# schmequencer.net
KiCad netlist of a schematic drawn in EAGLE
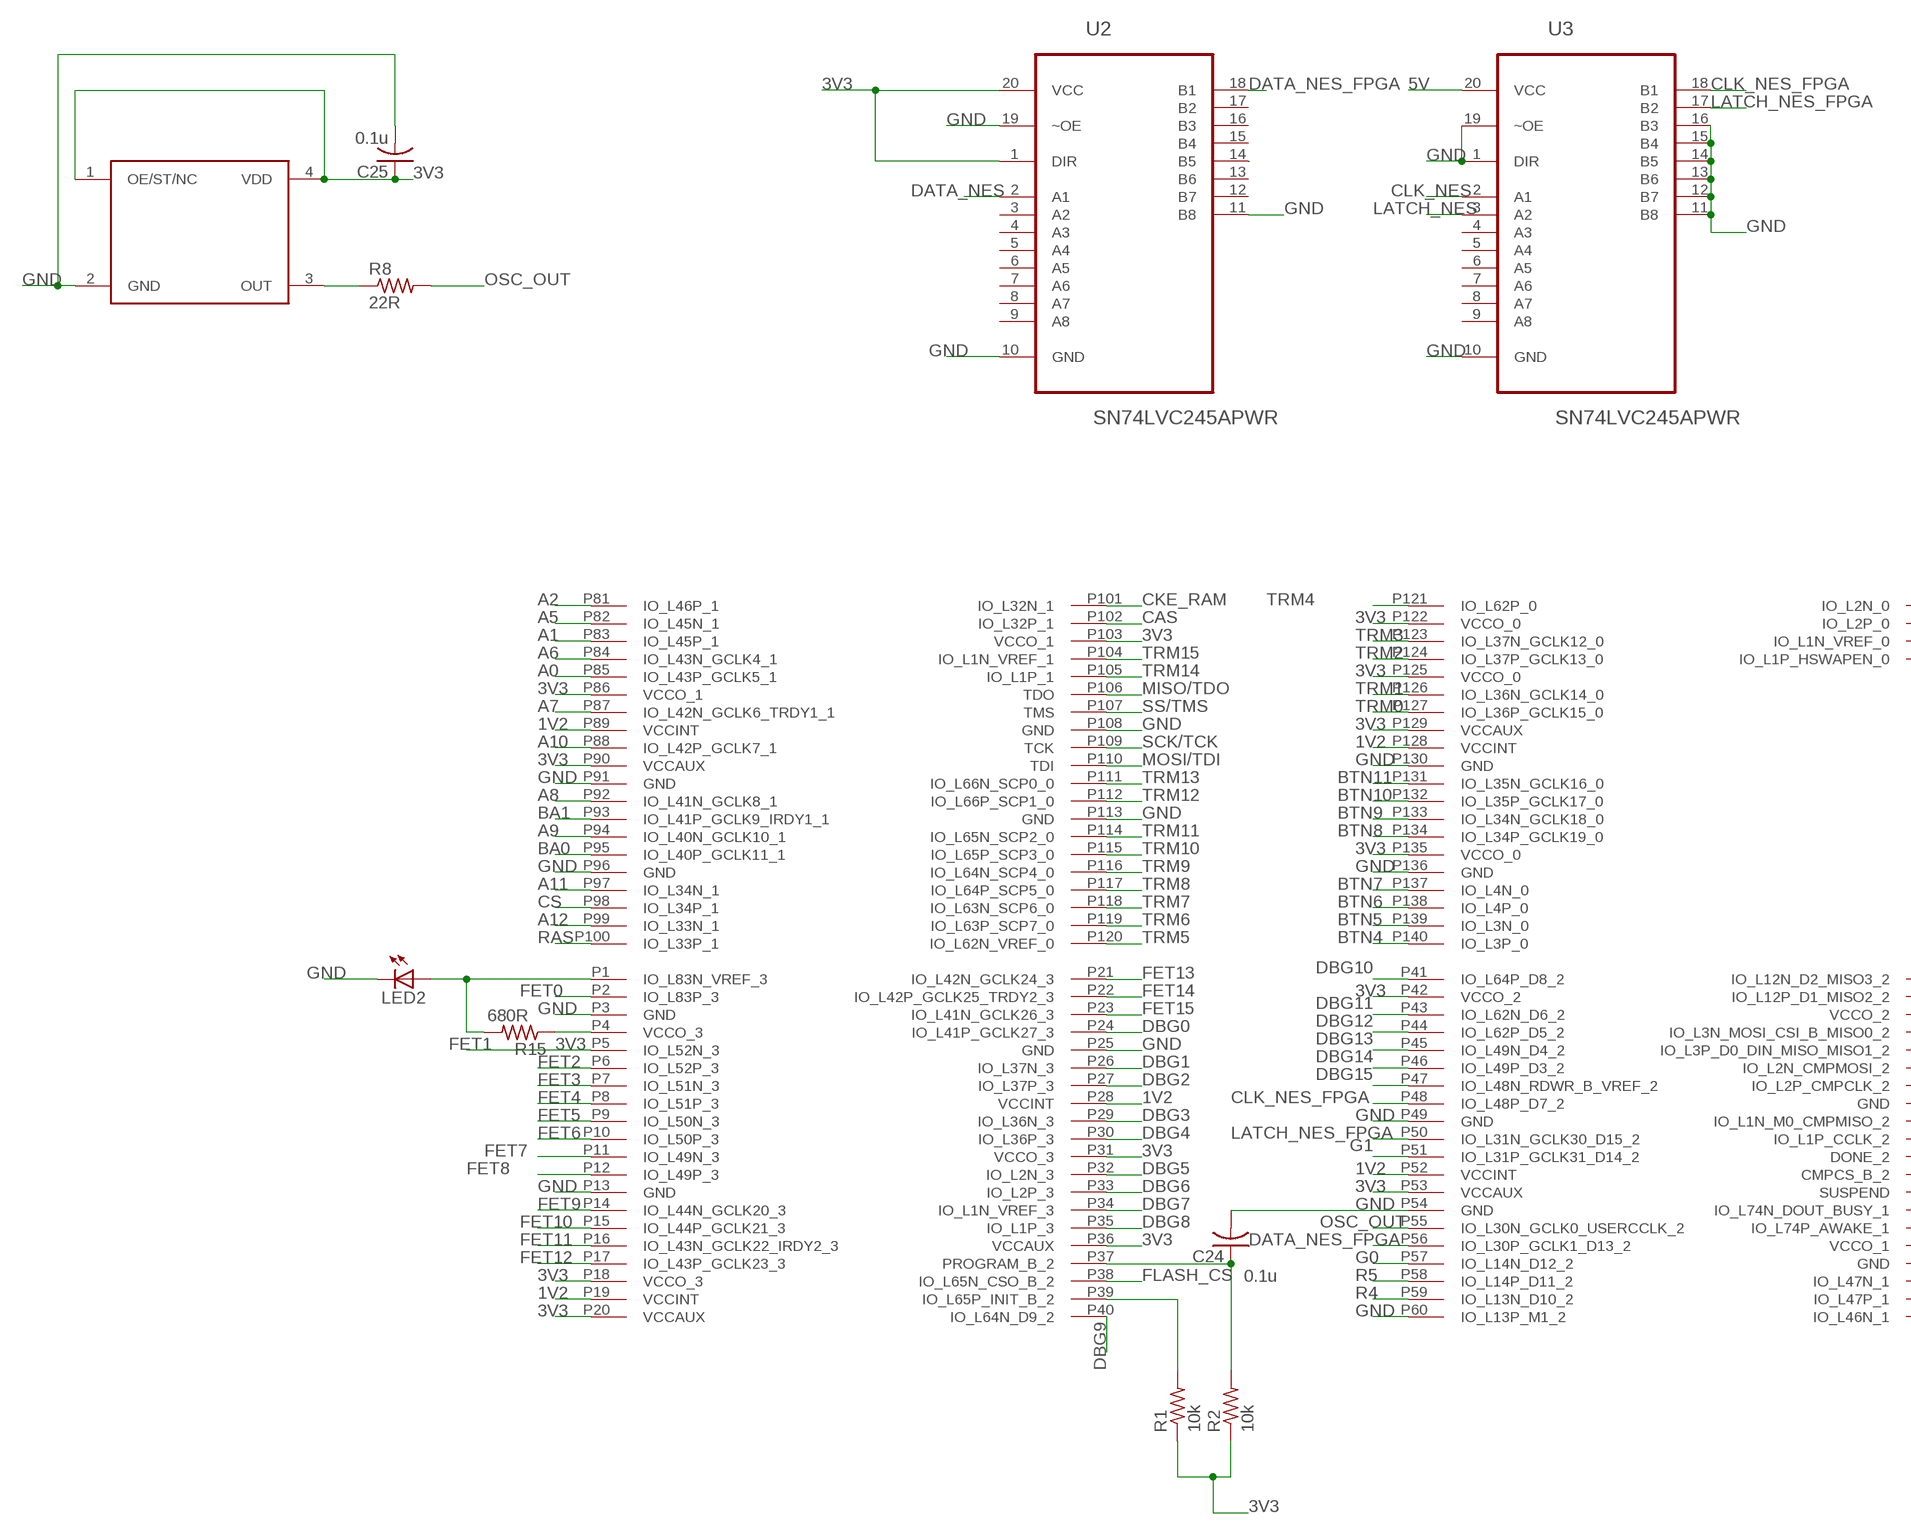
[diagram p0: schematic, sheet 1, part 1 of 2]
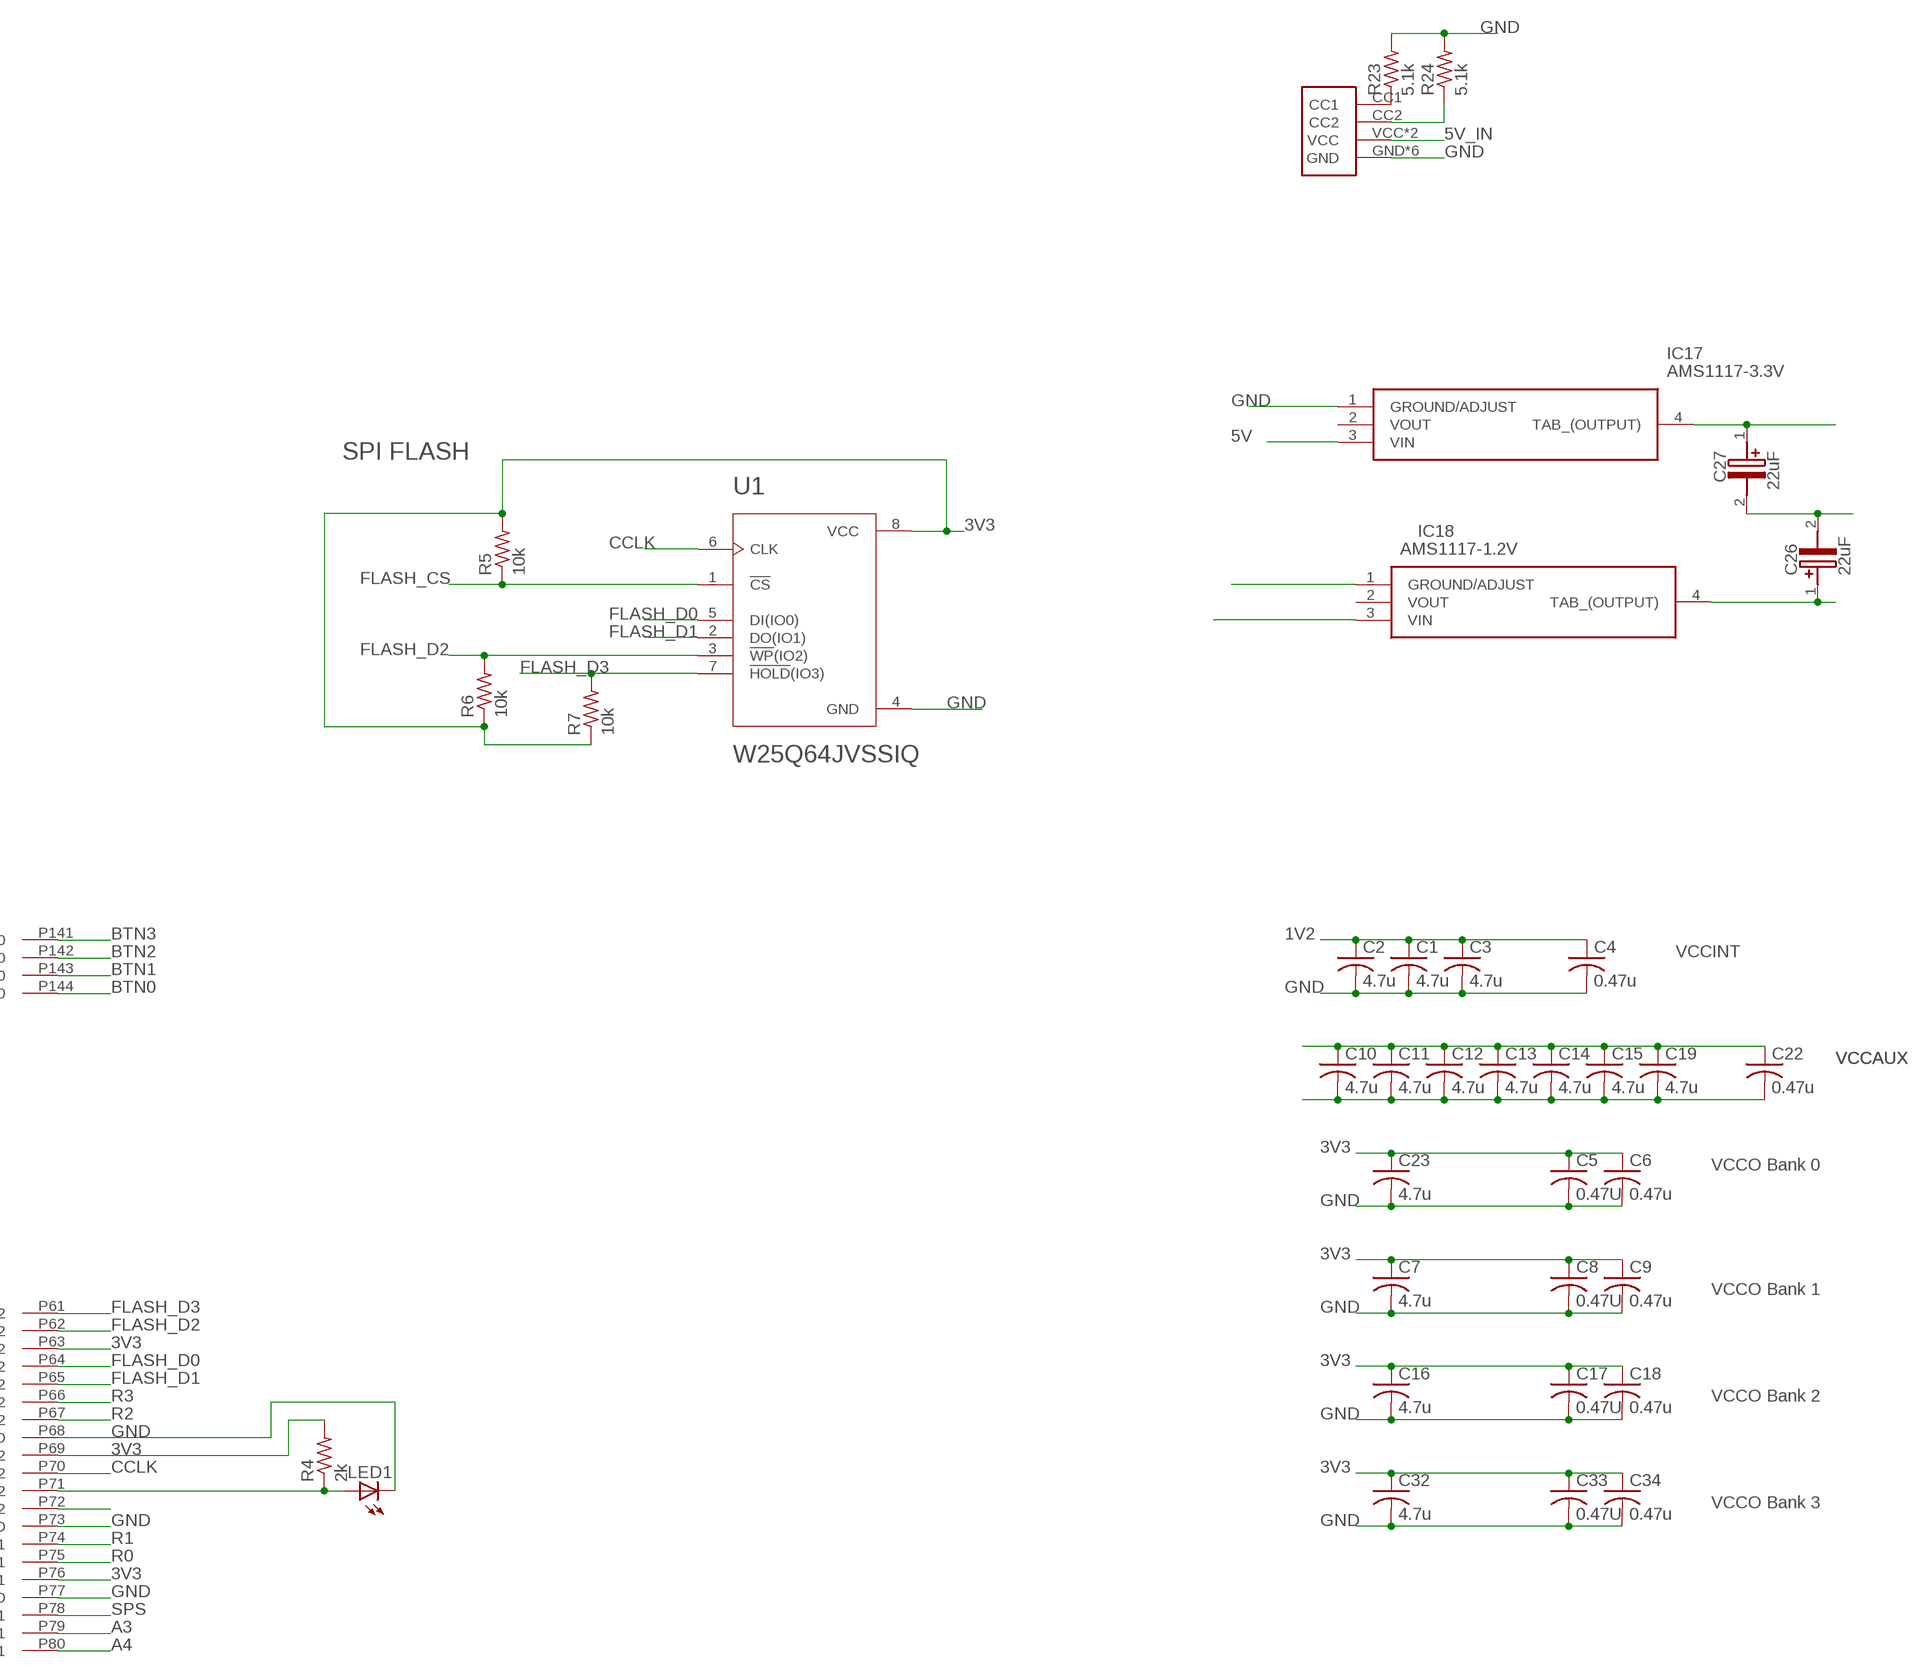
[diagram p1: schematic, sheet 1, part 2 of 2]
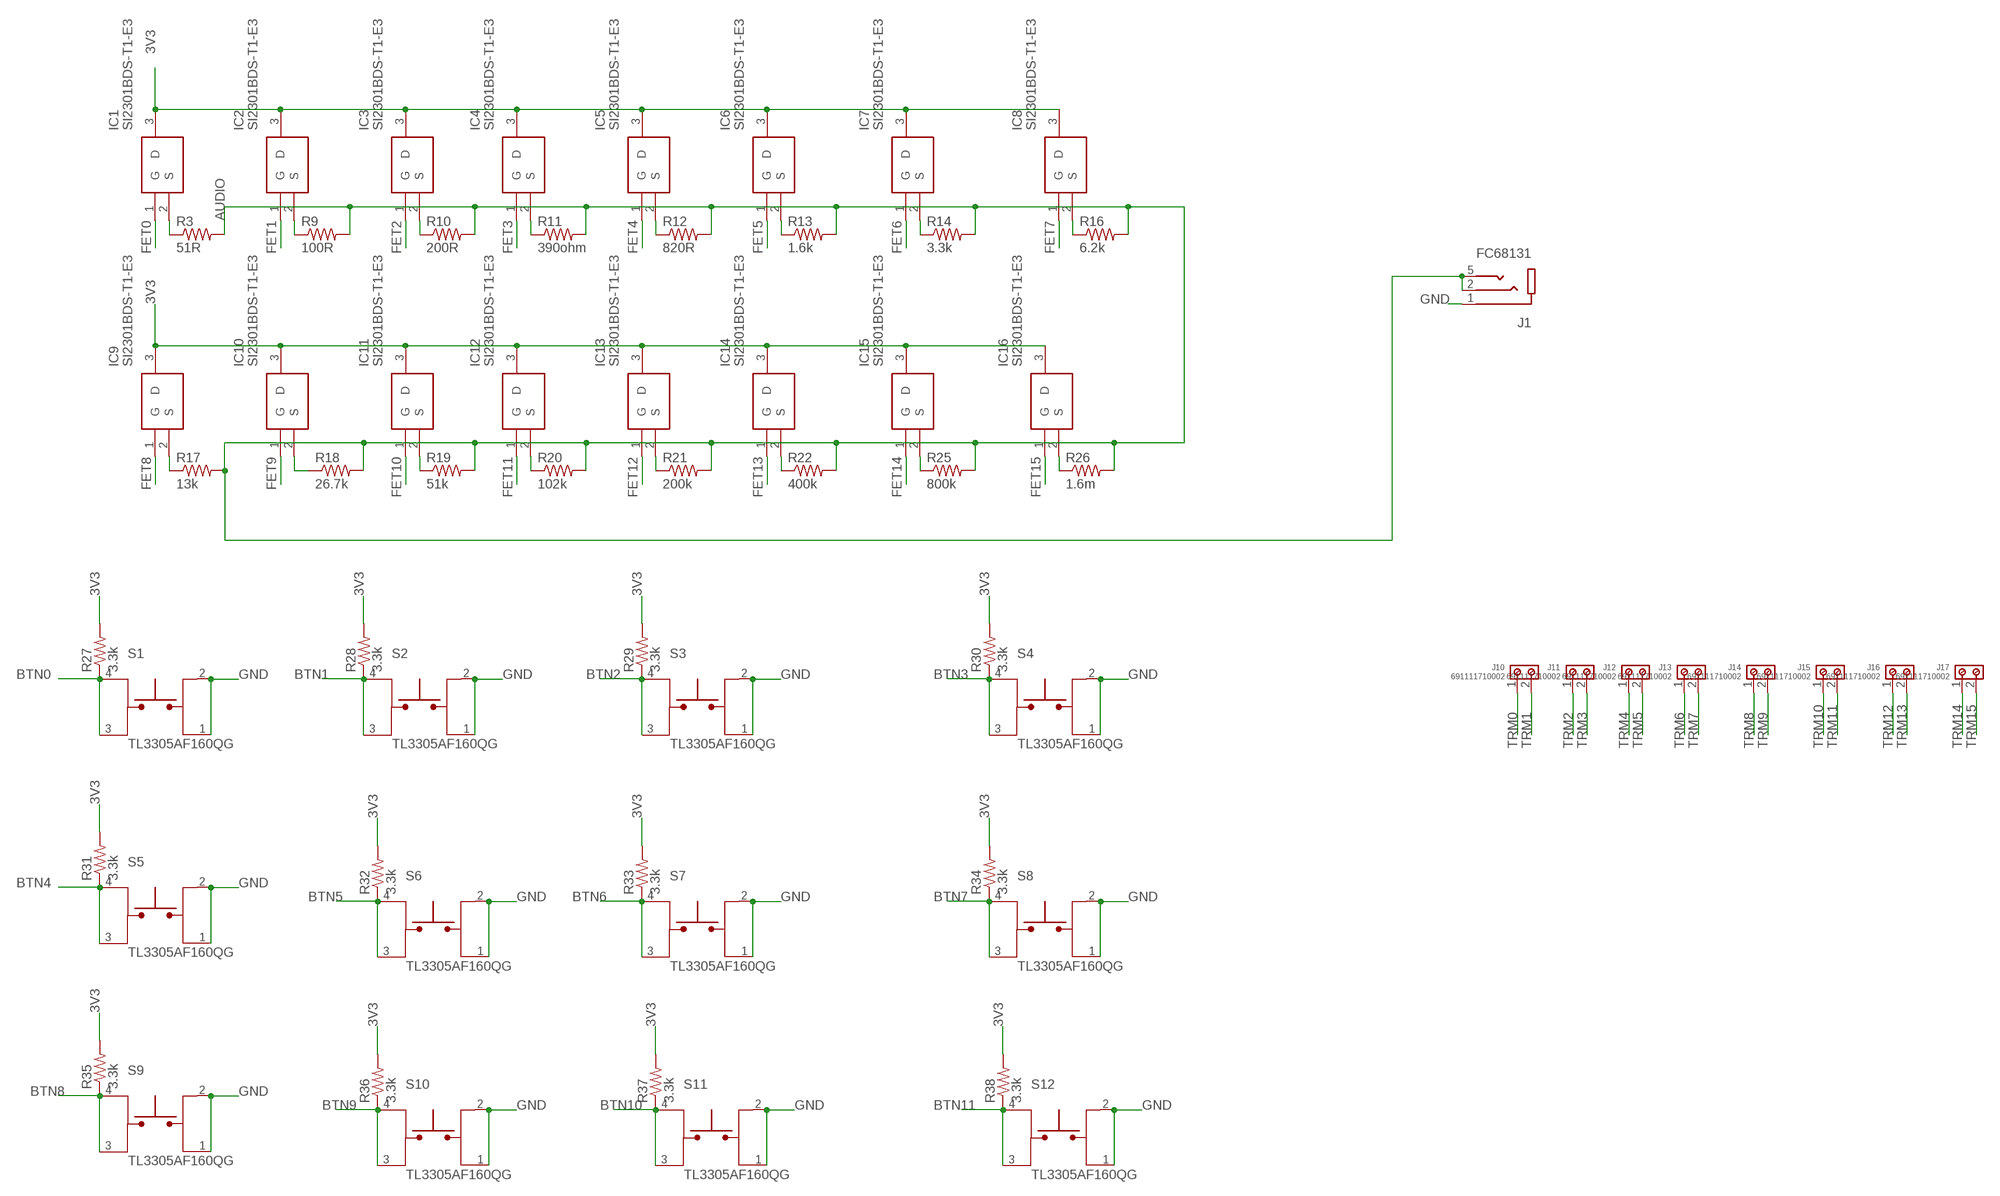
[diagram p2: schematic, sheet 2]
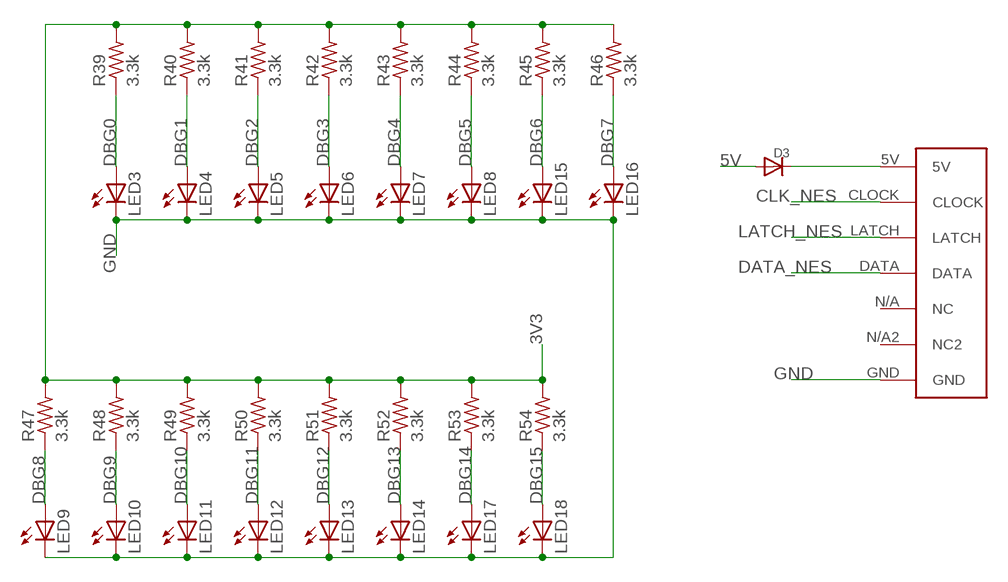
[diagram p3: schematic, sheet 3]

(export (version "E")
  (design (tool "Eeschema 10.0.6"))
  (components
    (comp (ref "C1")
      (value "4.7u")
      (footprint "eagle-import:C0603")
      (libsource (lib "eagle-import") (part "C-USC0603"))
    )
    (comp (ref "C2")
      (value "4.7u")
      (footprint "eagle-import:C0603")
      (libsource (lib "eagle-import") (part "C-USC0603"))
    )
    (comp (ref "C3")
      (value "4.7u")
      (footprint "eagle-import:C0603")
      (libsource (lib "eagle-import") (part "C-USC0603"))
    )
    (comp (ref "C4")
      (value "0.47u")
      (footprint "eagle-import:C0603")
      (libsource (lib "eagle-import") (part "C-USC0603"))
    )
    (comp (ref "C5")
      (value "0.47U")
      (footprint "eagle-import:C0603")
      (libsource (lib "eagle-import") (part "C-USC0603"))
    )
    (comp (ref "C6")
      (value "0.47u")
      (footprint "eagle-import:C0603")
      (libsource (lib "eagle-import") (part "C-USC0603"))
    )
    (comp (ref "C7")
      (value "4.7u")
      (footprint "eagle-import:C0603")
      (libsource (lib "eagle-import") (part "C-USC0603"))
    )
    (comp (ref "C8")
      (value "0.47U")
      (footprint "eagle-import:C0603")
      (libsource (lib "eagle-import") (part "C-USC0603"))
    )
    (comp (ref "C9")
      (value "0.47u")
      (footprint "eagle-import:C0603")
      (libsource (lib "eagle-import") (part "C-USC0603"))
    )
    (comp (ref "C10")
      (value "4.7u")
      (footprint "eagle-import:C0603")
      (libsource (lib "eagle-import") (part "C-USC0603"))
    )
    (comp (ref "C11")
      (value "4.7u")
      (footprint "eagle-import:C0603")
      (libsource (lib "eagle-import") (part "C-USC0603"))
    )
    (comp (ref "C12")
      (value "4.7u")
      (footprint "eagle-import:C0603")
      (libsource (lib "eagle-import") (part "C-USC0603"))
    )
    (comp (ref "C13")
      (value "4.7u")
      (footprint "eagle-import:C0603")
      (libsource (lib "eagle-import") (part "C-USC0603"))
    )
    (comp (ref "C14")
      (value "4.7u")
      (footprint "eagle-import:C0603")
      (libsource (lib "eagle-import") (part "C-USC0603"))
    )
    (comp (ref "C15")
      (value "4.7u")
      (footprint "eagle-import:C0603")
      (libsource (lib "eagle-import") (part "C-USC0603"))
    )
    (comp (ref "C16")
      (value "4.7u")
      (footprint "eagle-import:C0603")
      (libsource (lib "eagle-import") (part "C-USC0603"))
    )
    (comp (ref "C17")
      (value "0.47U")
      (footprint "eagle-import:C0603")
      (libsource (lib "eagle-import") (part "C-USC0603"))
    )
    (comp (ref "C18")
      (value "0.47u")
      (footprint "eagle-import:C0603")
      (libsource (lib "eagle-import") (part "C-USC0603"))
    )
    (comp (ref "C19")
      (value "4.7u")
      (footprint "eagle-import:C0603")
      (libsource (lib "eagle-import") (part "C-USC0603"))
    )
    (comp (ref "C22")
      (value "0.47u")
      (footprint "eagle-import:C0603")
      (libsource (lib "eagle-import") (part "C-USC0603"))
    )
    (comp (ref "C23")
      (value "4.7u")
      (footprint "eagle-import:C0603")
      (libsource (lib "eagle-import") (part "C-USC0603"))
    )
    (comp (ref "C24")
      (value "0.1u")
      (footprint "eagle-import:C0603")
      (libsource (lib "eagle-import") (part "C-USC0603"))
    )
    (comp (ref "C25")
      (value "0.1u")
      (footprint "eagle-import:C0603")
      (libsource (lib "eagle-import") (part "C-USC0603"))
    )
    (comp (ref "C26")
      (value "22uF")
      (footprint "eagle-import:CAPPM3216X180N")
      (fields
        (field (name "MANUFACTURER_PART_NUMBER") "293D106X9016A2TE3")
        (field (name "MOUSER2_PART_NUMBER") "74-293D106X9016A2TE3")
      )
      (libsource (lib "eagle-import") (part "293D106X9016A2TE3"))
    )
    (comp (ref "C27")
      (value "22uF")
      (footprint "eagle-import:CAPPM3216X180N")
      (fields
        (field (name "MANUFACTURER_PART_NUMBER") "293D106X9016A2TE3")
        (field (name "MOUSER2_PART_NUMBER") "74-293D106X9016A2TE3")
      )
      (libsource (lib "eagle-import") (part "293D106X9016A2TE3"))
    )
    (comp (ref "C32")
      (value "4.7u")
      (footprint "eagle-import:C0603")
      (libsource (lib "eagle-import") (part "C-USC0603"))
    )
    (comp (ref "C33")
      (value "0.47U")
      (footprint "eagle-import:C0603")
      (libsource (lib "eagle-import") (part "C-USC0603"))
    )
    (comp (ref "C34")
      (value "0.47u")
      (footprint "eagle-import:C0603")
      (libsource (lib "eagle-import") (part "C-USC0603"))
    )
    (comp (ref "IC17")
      (value "AMS1117-3.3V")
      (footprint "eagle-import:SOT229P700X180-4N")
      (fields (field (name "MANUFACTURER_PART_NUMBER") "ams1117-3.3v"))
      (libsource (lib "eagle-import") (part "AMS1117-3.3V"))
    )
    (comp (ref "IC18")
      (value "AMS1117-1.2V")
      (footprint "eagle-import:SOT229P700X180-4N")
      (fields (field (name "MANUFACTURER_PART_NUMBER") "ams1117-3.3v"))
      (libsource (lib "eagle-import") (part "AMS1117-3.3V"))
    )
    (comp (ref "LED1")
      (value "LEDCHIP-LED0603")
      (footprint "eagle-import:CHIP-LED0603")
      (libsource (lib "eagle-import") (part "LEDCHIP-LED0603"))
    )
    (comp (ref "LED2")
      (value "LEDCHIP-LED0603")
      (footprint "eagle-import:CHIP-LED0603")
      (libsource (lib "eagle-import") (part "LEDCHIP-LED0603"))
    )
    (comp (ref "R1")
      (value "10k")
      (footprint "eagle-import:R0603")
      (libsource (lib "eagle-import") (part "R-US_R0603"))
    )
    (comp (ref "R2")
      (value "10k")
      (footprint "eagle-import:R0603")
      (libsource (lib "eagle-import") (part "R-US_R0603"))
    )
    (comp (ref "R4")
      (value "2k")
      (footprint "eagle-import:R0603")
      (libsource (lib "eagle-import") (part "R-US_R0603"))
    )
    (comp (ref "R5")
      (value "10k")
      (footprint "eagle-import:R0603")
      (libsource (lib "eagle-import") (part "R-US_R0603"))
    )
    (comp (ref "R6")
      (value "10k")
      (footprint "eagle-import:R0603")
      (libsource (lib "eagle-import") (part "R-US_R0603"))
    )
    (comp (ref "R7")
      (value "10k")
      (footprint "eagle-import:R0603")
      (libsource (lib "eagle-import") (part "R-US_R0603"))
    )
    (comp (ref "R8")
      (value "22R")
      (footprint "eagle-import:R0603")
      (libsource (lib "eagle-import") (part "resistor_348_R-US_R0603"))
    )
    (comp (ref "R15")
      (value "680R")
      (footprint "eagle-import:R0603")
      (libsource (lib "eagle-import") (part "R-US_R0603"))
    )
    (comp (ref "R23")
      (value "5.1k")
      (footprint "eagle-import:R0603")
      (libsource (lib "eagle-import") (part "R-US_R0603"))
    )
    (comp (ref "R24")
      (value "5.1k")
      (footprint "eagle-import:R0603")
      (libsource (lib "eagle-import") (part "R-US_R0603"))
    )
    (comp (ref "U$1")
      (value "O50327425MEDH4MI")
      (footprint "eagle-import:OSC_ECS-3518-640-B-TR")
      (libsource (lib "eagle-import") (part "SIT1602BI-82-33E-75.250000YO50327425MEDH4MI"))
    )
    (comp (ref "U$2")
      (value "XC6SLX9-2TQG144C")
      (footprint "eagle-import:TQ144")
      (fields (field (name "MF") "Xilinx Inc."))
      (libsource (lib "eagle-import") (part "XC6SLX9-2TQG144C"))
    )
    (comp (ref "U$7")
      (value "POWER_USBC")
      (footprint "eagle-import:USB-C")
      (libsource (lib "eagle-import") (part "POWER_USBC"))
    )
    (comp (ref "U1")
      (value "W25Q64JVSSIQ")
      (footprint "eagle-import:SOIC127P790X216-8N")
      (fields (field (name "MF") "Winbond Electronics") (field (name "MP") "W25Q64BVSSIG"))
      (libsource (lib "eagle-import") (part "W25Q64BVSSIG"))
    )
    (comp (ref "U2")
      (value "SN74LVC245APWR")
      (footprint "eagle-import:SOP65P640X120-20N")
      (fields (field (name "DIGI-KEY_PART_NUMBER") "296-1233-1-ND") (field (name "MF") "Texas Instruments"))
      (libsource (lib "eagle-import") (part "SN74LVC245APWR"))
    )
    (comp (ref "U3")
      (value "SN74LVC245APWR")
      (footprint "eagle-import:SOP65P640X120-20N")
      (fields (field (name "DIGI-KEY_PART_NUMBER") "296-1233-1-ND") (field (name "MF") "Texas Instruments"))
      (libsource (lib "eagle-import") (part "SN74LVC245APWR"))
    )
    (comp (ref "IC1")
      (value "SI2301BDS-T1-E3")
      (footprint "eagle-import:SOT95P237X112-3N")
      (fields (field (name "MOUSER2_PART_NUMBER") "781-SI2301BDS-E3"))
      (libsource (lib "eagle-import") (part "SI2301BDS-T1-E3"))
    )
    (comp (ref "IC2")
      (value "SI2301BDS-T1-E3")
      (footprint "eagle-import:SOT95P237X112-3N")
      (fields (field (name "MOUSER2_PART_NUMBER") "781-SI2301BDS-E3"))
      (libsource (lib "eagle-import") (part "SI2301BDS-T1-E3"))
    )
    (comp (ref "IC3")
      (value "SI2301BDS-T1-E3")
      (footprint "eagle-import:SOT95P237X112-3N")
      (fields (field (name "MOUSER2_PART_NUMBER") "781-SI2301BDS-E3"))
      (libsource (lib "eagle-import") (part "SI2301BDS-T1-E3"))
    )
    (comp (ref "IC4")
      (value "SI2301BDS-T1-E3")
      (footprint "eagle-import:SOT95P237X112-3N")
      (fields (field (name "MOUSER2_PART_NUMBER") "781-SI2301BDS-E3"))
      (libsource (lib "eagle-import") (part "SI2301BDS-T1-E3"))
    )
    (comp (ref "IC5")
      (value "SI2301BDS-T1-E3")
      (footprint "eagle-import:SOT95P237X112-3N")
      (fields (field (name "MOUSER2_PART_NUMBER") "781-SI2301BDS-E3"))
      (libsource (lib "eagle-import") (part "SI2301BDS-T1-E3"))
    )
    (comp (ref "IC6")
      (value "SI2301BDS-T1-E3")
      (footprint "eagle-import:SOT95P237X112-3N")
      (fields (field (name "MOUSER2_PART_NUMBER") "781-SI2301BDS-E3"))
      (libsource (lib "eagle-import") (part "SI2301BDS-T1-E3"))
    )
    (comp (ref "IC7")
      (value "SI2301BDS-T1-E3")
      (footprint "eagle-import:SOT95P237X112-3N")
      (fields (field (name "MOUSER2_PART_NUMBER") "781-SI2301BDS-E3"))
      (libsource (lib "eagle-import") (part "SI2301BDS-T1-E3"))
    )
    (comp (ref "IC8")
      (value "SI2301BDS-T1-E3")
      (footprint "eagle-import:SOT95P237X112-3N")
      (fields (field (name "MOUSER2_PART_NUMBER") "781-SI2301BDS-E3"))
      (libsource (lib "eagle-import") (part "SI2301BDS-T1-E3"))
    )
    (comp (ref "IC9")
      (value "SI2301BDS-T1-E3")
      (footprint "eagle-import:SOT95P237X112-3N")
      (fields (field (name "MOUSER2_PART_NUMBER") "781-SI2301BDS-E3"))
      (libsource (lib "eagle-import") (part "SI2301BDS-T1-E3"))
    )
    (comp (ref "IC10")
      (value "SI2301BDS-T1-E3")
      (footprint "eagle-import:SOT95P237X112-3N")
      (fields (field (name "MOUSER2_PART_NUMBER") "781-SI2301BDS-E3"))
      (libsource (lib "eagle-import") (part "SI2301BDS-T1-E3"))
    )
    (comp (ref "IC11")
      (value "SI2301BDS-T1-E3")
      (footprint "eagle-import:SOT95P237X112-3N")
      (fields (field (name "MOUSER2_PART_NUMBER") "781-SI2301BDS-E3"))
      (libsource (lib "eagle-import") (part "SI2301BDS-T1-E3"))
    )
    (comp (ref "IC12")
      (value "SI2301BDS-T1-E3")
      (footprint "eagle-import:SOT95P237X112-3N")
      (fields (field (name "MOUSER2_PART_NUMBER") "781-SI2301BDS-E3"))
      (libsource (lib "eagle-import") (part "SI2301BDS-T1-E3"))
    )
    (comp (ref "IC13")
      (value "SI2301BDS-T1-E3")
      (footprint "eagle-import:SOT95P237X112-3N")
      (fields (field (name "MOUSER2_PART_NUMBER") "781-SI2301BDS-E3"))
      (libsource (lib "eagle-import") (part "SI2301BDS-T1-E3"))
    )
    (comp (ref "IC14")
      (value "SI2301BDS-T1-E3")
      (footprint "eagle-import:SOT95P237X112-3N")
      (fields (field (name "MOUSER2_PART_NUMBER") "781-SI2301BDS-E3"))
      (libsource (lib "eagle-import") (part "SI2301BDS-T1-E3"))
    )
    (comp (ref "IC15")
      (value "SI2301BDS-T1-E3")
      (footprint "eagle-import:SOT95P237X112-3N")
      (fields (field (name "MOUSER2_PART_NUMBER") "781-SI2301BDS-E3"))
      (libsource (lib "eagle-import") (part "SI2301BDS-T1-E3"))
    )
    (comp (ref "IC16")
      (value "SI2301BDS-T1-E3")
      (footprint "eagle-import:SOT95P237X112-3N")
      (fields (field (name "MOUSER2_PART_NUMBER") "781-SI2301BDS-E3"))
      (libsource (lib "eagle-import") (part "SI2301BDS-T1-E3"))
    )
    (comp (ref "J1")
      (value "FC68131")
      (footprint "eagle-import:CLIFF_FC68131")
      (fields (field (name "MF") "Cliff"))
      (libsource (lib "eagle-import") (part "FC68131"))
    )
    (comp (ref "J10")
      (value "691111710002")
      (footprint "eagle-import:691111710002")
      (fields (field (name "MF") "Wurth Electronics"))
      (libsource (lib "eagle-import") (part "691111710002"))
    )
    (comp (ref "J11")
      (value "691111710002")
      (footprint "eagle-import:691111710002")
      (fields (field (name "MF") "Wurth Electronics"))
      (libsource (lib "eagle-import") (part "691111710002"))
    )
    (comp (ref "J12")
      (value "691111710002")
      (footprint "eagle-import:691111710002")
      (fields (field (name "MF") "Wurth Electronics"))
      (libsource (lib "eagle-import") (part "691111710002"))
    )
    (comp (ref "J13")
      (value "691111710002")
      (footprint "eagle-import:691111710002")
      (fields (field (name "MF") "Wurth Electronics"))
      (libsource (lib "eagle-import") (part "691111710002"))
    )
    (comp (ref "J14")
      (value "691111710002")
      (footprint "eagle-import:691111710002")
      (fields (field (name "MF") "Wurth Electronics"))
      (libsource (lib "eagle-import") (part "691111710002"))
    )
    (comp (ref "J15")
      (value "691111710002")
      (footprint "eagle-import:691111710002")
      (fields (field (name "MF") "Wurth Electronics"))
      (libsource (lib "eagle-import") (part "691111710002"))
    )
    (comp (ref "J16")
      (value "691111710002")
      (footprint "eagle-import:691111710002")
      (fields (field (name "MF") "Wurth Electronics"))
      (libsource (lib "eagle-import") (part "691111710002"))
    )
    (comp (ref "J17")
      (value "691111710002")
      (footprint "eagle-import:691111710002")
      (fields (field (name "MF") "Wurth Electronics"))
      (libsource (lib "eagle-import") (part "691111710002"))
    )
    (comp (ref "R3")
      (value "51R")
      (footprint "eagle-import:R0805")
      (libsource (lib "eagle-import") (part "R-US_R0805"))
    )
    (comp (ref "R9")
      (value "100R")
      (footprint "eagle-import:R0805")
      (libsource (lib "eagle-import") (part "R-US_R0805"))
    )
    (comp (ref "R10")
      (value "200R")
      (footprint "eagle-import:R0805")
      (libsource (lib "eagle-import") (part "R-US_R0805"))
    )
    (comp (ref "R11")
      (value "390ohm")
      (footprint "eagle-import:R0805")
      (libsource (lib "eagle-import") (part "R-US_R0805"))
    )
    (comp (ref "R12")
      (value "820R")
      (footprint "eagle-import:R0805")
      (libsource (lib "eagle-import") (part "R-US_R0805"))
    )
    (comp (ref "R13")
      (value "1.6k")
      (footprint "eagle-import:R0805")
      (libsource (lib "eagle-import") (part "R-US_R0805"))
    )
    (comp (ref "R14")
      (value "3.3k")
      (footprint "eagle-import:R0805")
      (libsource (lib "eagle-import") (part "R-US_R0805"))
    )
    (comp (ref "R16")
      (value "6.2k")
      (footprint "eagle-import:R0805")
      (libsource (lib "eagle-import") (part "R-US_R0805"))
    )
    (comp (ref "R17")
      (value "13k")
      (footprint "eagle-import:R0805")
      (libsource (lib "eagle-import") (part "R-US_R0805"))
    )
    (comp (ref "R18")
      (value "26.7k")
      (footprint "eagle-import:R0805")
      (libsource (lib "eagle-import") (part "R-US_R0805"))
    )
    (comp (ref "R19")
      (value "51k")
      (footprint "eagle-import:R0805")
      (libsource (lib "eagle-import") (part "R-US_R0805"))
    )
    (comp (ref "R20")
      (value "102k")
      (footprint "eagle-import:R0805")
      (libsource (lib "eagle-import") (part "R-US_R0805"))
    )
    (comp (ref "R21")
      (value "200k")
      (footprint "eagle-import:R0805")
      (libsource (lib "eagle-import") (part "R-US_R0805"))
    )
    (comp (ref "R22")
      (value "400k")
      (footprint "eagle-import:R0805")
      (libsource (lib "eagle-import") (part "R-US_R0805"))
    )
    (comp (ref "R25")
      (value "800k")
      (footprint "eagle-import:R0805")
      (libsource (lib "eagle-import") (part "R-US_R0805"))
    )
    (comp (ref "R26")
      (value "1.6m")
      (footprint "eagle-import:R0805")
      (libsource (lib "eagle-import") (part "R-US_R0805"))
    )
    (comp (ref "R27")
      (value "3.3k")
      (footprint "eagle-import:R0805")
      (libsource (lib "eagle-import") (part "R-US_R0805"))
    )
    (comp (ref "R28")
      (value "3.3k")
      (footprint "eagle-import:R0805")
      (libsource (lib "eagle-import") (part "R-US_R0805"))
    )
    (comp (ref "R29")
      (value "3.3k")
      (footprint "eagle-import:R0805")
      (libsource (lib "eagle-import") (part "R-US_R0805"))
    )
    (comp (ref "R30")
      (value "3.3k")
      (footprint "eagle-import:R0805")
      (libsource (lib "eagle-import") (part "R-US_R0805"))
    )
    (comp (ref "R31")
      (value "3.3k")
      (footprint "eagle-import:R0805")
      (libsource (lib "eagle-import") (part "R-US_R0805"))
    )
    (comp (ref "R32")
      (value "3.3k")
      (footprint "eagle-import:R0805")
      (libsource (lib "eagle-import") (part "R-US_R0805"))
    )
    (comp (ref "R33")
      (value "3.3k")
      (footprint "eagle-import:R0805")
      (libsource (lib "eagle-import") (part "R-US_R0805"))
    )
    (comp (ref "R34")
      (value "3.3k")
      (footprint "eagle-import:R0805")
      (libsource (lib "eagle-import") (part "R-US_R0805"))
    )
    (comp (ref "R35")
      (value "3.3k")
      (footprint "eagle-import:R0805")
      (libsource (lib "eagle-import") (part "R-US_R0805"))
    )
    (comp (ref "R36")
      (value "3.3k")
      (footprint "eagle-import:R0805")
      (libsource (lib "eagle-import") (part "R-US_R0805"))
    )
    (comp (ref "R37")
      (value "3.3k")
      (footprint "eagle-import:R0805")
      (libsource (lib "eagle-import") (part "R-US_R0805"))
    )
    (comp (ref "R38")
      (value "3.3k")
      (footprint "eagle-import:R0805")
      (libsource (lib "eagle-import") (part "R-US_R0805"))
    )
    (comp (ref "S1")
      (value "TL3305AF160QG")
      (footprint "eagle-import:SW_TL3305AF160QG")
      (fields (field (name "MF") "E-Switch"))
      (libsource (lib "eagle-import") (part "TL3305AF160QG"))
    )
    (comp (ref "S2")
      (value "TL3305AF160QG")
      (footprint "eagle-import:SW_TL3305AF160QG")
      (fields (field (name "MF") "E-Switch"))
      (libsource (lib "eagle-import") (part "TL3305AF160QG"))
    )
    (comp (ref "S3")
      (value "TL3305AF160QG")
      (footprint "eagle-import:SW_TL3305AF160QG")
      (fields (field (name "MF") "E-Switch"))
      (libsource (lib "eagle-import") (part "TL3305AF160QG"))
    )
    (comp (ref "S4")
      (value "TL3305AF160QG")
      (footprint "eagle-import:SW_TL3305AF160QG")
      (fields (field (name "MF") "E-Switch"))
      (libsource (lib "eagle-import") (part "TL3305AF160QG"))
    )
    (comp (ref "S5")
      (value "TL3305AF160QG")
      (footprint "eagle-import:SW_TL3305AF160QG")
      (fields (field (name "MF") "E-Switch"))
      (libsource (lib "eagle-import") (part "TL3305AF160QG"))
    )
    (comp (ref "S6")
      (value "TL3305AF160QG")
      (footprint "eagle-import:SW_TL3305AF160QG")
      (fields (field (name "MF") "E-Switch"))
      (libsource (lib "eagle-import") (part "TL3305AF160QG"))
    )
    (comp (ref "S7")
      (value "TL3305AF160QG")
      (footprint "eagle-import:SW_TL3305AF160QG")
      (fields (field (name "MF") "E-Switch"))
      (libsource (lib "eagle-import") (part "TL3305AF160QG"))
    )
    (comp (ref "S8")
      (value "TL3305AF160QG")
      (footprint "eagle-import:SW_TL3305AF160QG")
      (fields (field (name "MF") "E-Switch"))
      (libsource (lib "eagle-import") (part "TL3305AF160QG"))
    )
    (comp (ref "S9")
      (value "TL3305AF160QG")
      (footprint "eagle-import:SW_TL3305AF160QG")
      (fields (field (name "MF") "E-Switch"))
      (libsource (lib "eagle-import") (part "TL3305AF160QG"))
    )
    (comp (ref "S10")
      (value "TL3305AF160QG")
      (footprint "eagle-import:SW_TL3305AF160QG")
      (fields (field (name "MF") "E-Switch"))
      (libsource (lib "eagle-import") (part "TL3305AF160QG"))
    )
    (comp (ref "S11")
      (value "TL3305AF160QG")
      (footprint "eagle-import:SW_TL3305AF160QG")
      (fields (field (name "MF") "E-Switch"))
      (libsource (lib "eagle-import") (part "TL3305AF160QG"))
    )
    (comp (ref "S12")
      (value "TL3305AF160QG")
      (footprint "eagle-import:SW_TL3305AF160QG")
      (fields (field (name "MF") "E-Switch"))
      (libsource (lib "eagle-import") (part "TL3305AF160QG"))
    )
    (comp (ref "D3")
      (value "DIODESOD-123")
      (footprint "eagle-import:SOD-123")
      (libsource (lib "eagle-import") (part "DIODESOD-123"))
    )
    (comp (ref "LED3")
      (value "LEDCHIP-LED0603")
      (footprint "eagle-import:CHIP-LED0603")
      (libsource (lib "eagle-import") (part "LEDCHIP-LED0603"))
    )
    (comp (ref "LED4")
      (value "LEDCHIP-LED0603")
      (footprint "eagle-import:CHIP-LED0603")
      (libsource (lib "eagle-import") (part "LEDCHIP-LED0603"))
    )
    (comp (ref "LED5")
      (value "LEDCHIP-LED0603")
      (footprint "eagle-import:CHIP-LED0603")
      (libsource (lib "eagle-import") (part "LEDCHIP-LED0603"))
    )
    (comp (ref "LED6")
      (value "LEDCHIP-LED0603")
      (footprint "eagle-import:CHIP-LED0603")
      (libsource (lib "eagle-import") (part "LEDCHIP-LED0603"))
    )
    (comp (ref "LED7")
      (value "LEDCHIP-LED0603")
      (footprint "eagle-import:CHIP-LED0603")
      (libsource (lib "eagle-import") (part "LEDCHIP-LED0603"))
    )
    (comp (ref "LED8")
      (value "LEDCHIP-LED0603")
      (footprint "eagle-import:CHIP-LED0603")
      (libsource (lib "eagle-import") (part "LEDCHIP-LED0603"))
    )
    (comp (ref "LED9")
      (value "LEDCHIP-LED0603")
      (footprint "eagle-import:CHIP-LED0603")
      (libsource (lib "eagle-import") (part "LEDCHIP-LED0603"))
    )
    (comp (ref "LED10")
      (value "LEDCHIP-LED0603")
      (footprint "eagle-import:CHIP-LED0603")
      (libsource (lib "eagle-import") (part "LEDCHIP-LED0603"))
    )
    (comp (ref "LED11")
      (value "LEDCHIP-LED0603")
      (footprint "eagle-import:CHIP-LED0603")
      (libsource (lib "eagle-import") (part "LEDCHIP-LED0603"))
    )
    (comp (ref "LED12")
      (value "LEDCHIP-LED0603")
      (footprint "eagle-import:CHIP-LED0603")
      (libsource (lib "eagle-import") (part "LEDCHIP-LED0603"))
    )
    (comp (ref "LED13")
      (value "LEDCHIP-LED0603")
      (footprint "eagle-import:CHIP-LED0603")
      (libsource (lib "eagle-import") (part "LEDCHIP-LED0603"))
    )
    (comp (ref "LED14")
      (value "LEDCHIP-LED0603")
      (footprint "eagle-import:CHIP-LED0603")
      (libsource (lib "eagle-import") (part "LEDCHIP-LED0603"))
    )
    (comp (ref "LED15")
      (value "LEDCHIP-LED0603")
      (footprint "eagle-import:CHIP-LED0603")
      (libsource (lib "eagle-import") (part "LEDCHIP-LED0603"))
    )
    (comp (ref "LED16")
      (value "LEDCHIP-LED0603")
      (footprint "eagle-import:CHIP-LED0603")
      (libsource (lib "eagle-import") (part "LEDCHIP-LED0603"))
    )
    (comp (ref "LED17")
      (value "LEDCHIP-LED0603")
      (footprint "eagle-import:CHIP-LED0603")
      (libsource (lib "eagle-import") (part "LEDCHIP-LED0603"))
    )
    (comp (ref "LED18")
      (value "LEDCHIP-LED0603")
      (footprint "eagle-import:CHIP-LED0603")
      (libsource (lib "eagle-import") (part "LEDCHIP-LED0603"))
    )
    (comp (ref "R39")
      (value "3.3k")
      (footprint "eagle-import:R0805")
      (libsource (lib "eagle-import") (part "R-US_R0805"))
    )
    (comp (ref "R40")
      (value "3.3k")
      (footprint "eagle-import:R0805")
      (libsource (lib "eagle-import") (part "R-US_R0805"))
    )
    (comp (ref "R41")
      (value "3.3k")
      (footprint "eagle-import:R0805")
      (libsource (lib "eagle-import") (part "R-US_R0805"))
    )
    (comp (ref "R42")
      (value "3.3k")
      (footprint "eagle-import:R0805")
      (libsource (lib "eagle-import") (part "R-US_R0805"))
    )
    (comp (ref "R43")
      (value "3.3k")
      (footprint "eagle-import:R0805")
      (libsource (lib "eagle-import") (part "R-US_R0805"))
    )
    (comp (ref "R44")
      (value "3.3k")
      (footprint "eagle-import:R0805")
      (libsource (lib "eagle-import") (part "R-US_R0805"))
    )
    (comp (ref "R45")
      (value "3.3k")
      (footprint "eagle-import:R0805")
      (libsource (lib "eagle-import") (part "R-US_R0805"))
    )
    (comp (ref "R46")
      (value "3.3k")
      (footprint "eagle-import:R0805")
      (libsource (lib "eagle-import") (part "R-US_R0805"))
    )
    (comp (ref "R47")
      (value "3.3k")
      (footprint "eagle-import:R0805")
      (libsource (lib "eagle-import") (part "R-US_R0805"))
    )
    (comp (ref "R48")
      (value "3.3k")
      (footprint "eagle-import:R0805")
      (libsource (lib "eagle-import") (part "R-US_R0805"))
    )
    (comp (ref "R49")
      (value "3.3k")
      (footprint "eagle-import:R0805")
      (libsource (lib "eagle-import") (part "R-US_R0805"))
    )
    (comp (ref "R50")
      (value "3.3k")
      (footprint "eagle-import:R0805")
      (libsource (lib "eagle-import") (part "R-US_R0805"))
    )
    (comp (ref "R51")
      (value "3.3k")
      (footprint "eagle-import:R0805")
      (libsource (lib "eagle-import") (part "R-US_R0805"))
    )
    (comp (ref "R52")
      (value "3.3k")
      (footprint "eagle-import:R0805")
      (libsource (lib "eagle-import") (part "R-US_R0805"))
    )
    (comp (ref "R53")
      (value "3.3k")
      (footprint "eagle-import:R0805")
      (libsource (lib "eagle-import") (part "R-US_R0805"))
    )
    (comp (ref "R54")
      (value "3.3k")
      (footprint "eagle-import:R0805")
      (libsource (lib "eagle-import") (part "R-US_R0805"))
    )
    (comp (ref "U$3")
      (value "SNES_CONT")
      (footprint "eagle-import:SNES_CONT")
      (libsource (lib "eagle-import") (part "SNES_CONT"))
    )
  )
  (nets
    (net (code "1") (name "1V2") (class "Default")
      (node (ref "C1") (pin "1") (pinfunction "1_1") (pintype "passive"))
      (node (ref "C2") (pin "1") (pinfunction "1_1") (pintype "passive"))
      (node (ref "C3") (pin "1") (pinfunction "1_1") (pintype "passive"))
      (node (ref "C4") (pin "1") (pinfunction "1_1") (pintype "passive"))
      (node (ref "U$2") (pin "P128") (pinfunction "VCCINT_P128") (pintype "bidirectional"))
      (node (ref "U$2") (pin "P19") (pinfunction "VCCINT_P19") (pintype "bidirectional"))
      (node (ref "U$2") (pin "P28") (pinfunction "VCCINT_P28") (pintype "bidirectional"))
      (node (ref "U$2") (pin "P52") (pinfunction "VCCINT_P52") (pintype "bidirectional"))
      (node (ref "U$2") (pin "P89") (pinfunction "VCCINT_P89") (pintype "bidirectional"))
    )
    (net (code "2") (name "3V3") (class "Default")
      (node (ref "C10") (pin "1") (pinfunction "1_1") (pintype "passive"))
      (node (ref "C11") (pin "1") (pinfunction "1_1") (pintype "passive"))
      (node (ref "C12") (pin "1") (pinfunction "1_1") (pintype "passive"))
      (node (ref "C13") (pin "1") (pinfunction "1_1") (pintype "passive"))
      (node (ref "C14") (pin "1") (pinfunction "1_1") (pintype "passive"))
      (node (ref "C15") (pin "1") (pinfunction "1_1") (pintype "passive"))
      (node (ref "C16") (pin "1") (pinfunction "1_1") (pintype "passive"))
      (node (ref "C17") (pin "1") (pinfunction "1_1") (pintype "passive"))
      (node (ref "C18") (pin "1") (pinfunction "1_1") (pintype "passive"))
      (node (ref "C19") (pin "1") (pinfunction "1_1") (pintype "passive"))
      (node (ref "C22") (pin "1") (pinfunction "1_1") (pintype "passive"))
      (node (ref "C23") (pin "1") (pinfunction "1_1") (pintype "passive"))
      (node (ref "C25") (pin "1") (pinfunction "1_1") (pintype "passive"))
      (node (ref "C32") (pin "1") (pinfunction "1_1") (pintype "passive"))
      (node (ref "C33") (pin "1") (pinfunction "1_1") (pintype "passive"))
      (node (ref "C34") (pin "1") (pinfunction "1_1") (pintype "passive"))
      (node (ref "C5") (pin "1") (pinfunction "1_1") (pintype "passive"))
      (node (ref "C6") (pin "1") (pinfunction "1_1") (pintype "passive"))
      (node (ref "C7") (pin "1") (pinfunction "1_1") (pintype "passive"))
      (node (ref "C8") (pin "1") (pinfunction "1_1") (pintype "passive"))
      (node (ref "C9") (pin "1") (pinfunction "1_1") (pintype "passive"))
      (node (ref "IC1") (pin "3") (pinfunction "D_3") (pintype "bidirectional"))
      (node (ref "IC10") (pin "3") (pinfunction "D_3") (pintype "bidirectional"))
      (node (ref "IC11") (pin "3") (pinfunction "D_3") (pintype "bidirectional"))
      (node (ref "IC12") (pin "3") (pinfunction "D_3") (pintype "bidirectional"))
      (node (ref "IC13") (pin "3") (pinfunction "D_3") (pintype "bidirectional"))
      (node (ref "IC14") (pin "3") (pinfunction "D_3") (pintype "bidirectional"))
      (node (ref "IC15") (pin "3") (pinfunction "D_3") (pintype "bidirectional"))
      (node (ref "IC16") (pin "3") (pinfunction "D_3") (pintype "bidirectional"))
      (node (ref "IC2") (pin "3") (pinfunction "D_3") (pintype "bidirectional"))
      (node (ref "IC3") (pin "3") (pinfunction "D_3") (pintype "bidirectional"))
      (node (ref "IC4") (pin "3") (pinfunction "D_3") (pintype "bidirectional"))
      (node (ref "IC5") (pin "3") (pinfunction "D_3") (pintype "bidirectional"))
      (node (ref "IC6") (pin "3") (pinfunction "D_3") (pintype "bidirectional"))
      (node (ref "IC7") (pin "3") (pinfunction "D_3") (pintype "bidirectional"))
      (node (ref "IC8") (pin "3") (pinfunction "D_3") (pintype "bidirectional"))
      (node (ref "IC9") (pin "3") (pinfunction "D_3") (pintype "bidirectional"))
      (node (ref "R1") (pin "1") (pinfunction "1_1") (pintype "passive"))
      (node (ref "R15") (pin "1") (pinfunction "1_1") (pintype "passive"))
      (node (ref "R2") (pin "1") (pinfunction "1_1") (pintype "passive"))
      (node (ref "R27") (pin "2") (pinfunction "2_2") (pintype "passive"))
      (node (ref "R28") (pin "2") (pinfunction "2_2") (pintype "passive"))
      (node (ref "R29") (pin "2") (pinfunction "2_2") (pintype "passive"))
      (node (ref "R30") (pin "2") (pinfunction "2_2") (pintype "passive"))
      (node (ref "R31") (pin "2") (pinfunction "2_2") (pintype "passive"))
      (node (ref "R32") (pin "2") (pinfunction "2_2") (pintype "passive"))
      (node (ref "R33") (pin "2") (pinfunction "2_2") (pintype "passive"))
      (node (ref "R34") (pin "2") (pinfunction "2_2") (pintype "passive"))
      (node (ref "R35") (pin "2") (pinfunction "2_2") (pintype "passive"))
      (node (ref "R36") (pin "2") (pinfunction "2_2") (pintype "passive"))
      (node (ref "R37") (pin "2") (pinfunction "2_2") (pintype "passive"))
      (node (ref "R38") (pin "2") (pinfunction "2_2") (pintype "passive"))
      (node (ref "R39") (pin "2") (pinfunction "2_2") (pintype "passive"))
      (node (ref "R4") (pin "2") (pinfunction "2_2") (pintype "passive"))
      (node (ref "R40") (pin "2") (pinfunction "2_2") (pintype "passive"))
      (node (ref "R41") (pin "2") (pinfunction "2_2") (pintype "passive"))
      (node (ref "R42") (pin "2") (pinfunction "2_2") (pintype "passive"))
      (node (ref "R43") (pin "2") (pinfunction "2_2") (pintype "passive"))
      (node (ref "R44") (pin "2") (pinfunction "2_2") (pintype "passive"))
      (node (ref "R45") (pin "2") (pinfunction "2_2") (pintype "passive"))
      (node (ref "R46") (pin "2") (pinfunction "2_2") (pintype "passive"))
      (node (ref "R47") (pin "2") (pinfunction "2_2") (pintype "passive"))
      (node (ref "R48") (pin "2") (pinfunction "2_2") (pintype "passive"))
      (node (ref "R49") (pin "2") (pinfunction "2_2") (pintype "passive"))
      (node (ref "R5") (pin "2") (pinfunction "2_2") (pintype "passive"))
      (node (ref "R50") (pin "2") (pinfunction "2_2") (pintype "passive"))
      (node (ref "R51") (pin "2") (pinfunction "2_2") (pintype "passive"))
      (node (ref "R52") (pin "2") (pinfunction "2_2") (pintype "passive"))
      (node (ref "R53") (pin "2") (pinfunction "2_2") (pintype "passive"))
      (node (ref "R54") (pin "2") (pinfunction "2_2") (pintype "passive"))
      (node (ref "R6") (pin "1") (pinfunction "1_1") (pintype "passive"))
      (node (ref "R7") (pin "1") (pinfunction "1_1") (pintype "passive"))
      (node (ref "U$1") (pin "1") (pinfunction "OE/ST/NC_1") (pintype "bidirectional"))
      (node (ref "U$1") (pin "4") (pinfunction "VDD_4") (pintype "bidirectional"))
      (node (ref "U$2") (pin "P103") (pinfunction "VCCO_1_P103") (pintype "bidirectional"))
      (node (ref "U$2") (pin "P122") (pinfunction "VCCO_0_P122") (pintype "bidirectional"))
      (node (ref "U$2") (pin "P125") (pinfunction "VCCO_0_P125") (pintype "bidirectional"))
      (node (ref "U$2") (pin "P129") (pinfunction "VCCAUX_P129") (pintype "bidirectional"))
      (node (ref "U$2") (pin "P135") (pinfunction "VCCO_0_P135") (pintype "bidirectional"))
      (node (ref "U$2") (pin "P18") (pinfunction "VCCO_3_P18") (pintype "bidirectional"))
      (node (ref "U$2") (pin "P20") (pinfunction "VCCAUX_P20") (pintype "bidirectional"))
      (node (ref "U$2") (pin "P31") (pinfunction "VCCO_3_P31") (pintype "bidirectional"))
      (node (ref "U$2") (pin "P36") (pinfunction "VCCAUX_P36") (pintype "bidirectional"))
      (node (ref "U$2") (pin "P4") (pinfunction "VCCO_3_P4") (pintype "bidirectional"))
      (node (ref "U$2") (pin "P42") (pinfunction "VCCO_2_P42") (pintype "bidirectional"))
      (node (ref "U$2") (pin "P53") (pinfunction "VCCAUX_P53") (pintype "bidirectional"))
      (node (ref "U$2") (pin "P63") (pinfunction "VCCO_2_P63") (pintype "bidirectional"))
      (node (ref "U$2") (pin "P69") (pinfunction "IO_L1N_M0_CMPMISO_2_P69") (pintype "bidirectional"))
      (node (ref "U$2") (pin "P76") (pinfunction "VCCO_1_P76") (pintype "bidirectional"))
      (node (ref "U$2") (pin "P86") (pinfunction "VCCO_1_P86") (pintype "bidirectional"))
      (node (ref "U$2") (pin "P90") (pinfunction "VCCAUX_P90") (pintype "bidirectional"))
      (node (ref "U1") (pin "8") (pinfunction "VCC_8") (pintype "power_in"))
      (node (ref "U2") (pin "1") (pinfunction "DIR_1") (pintype "input"))
      (node (ref "U2") (pin "20") (pinfunction "VCC_20") (pintype "power_in"))
    )
    (net (code "3") (name "5V") (class "Default")
      (node (ref "D3") (pin "A") (pinfunction "A_A") (pintype "passive"))
      (node (ref "IC17") (pin "3") (pinfunction "VIN_3") (pintype "bidirectional"))
      (node (ref "IC18") (pin "3") (pinfunction "VIN_3") (pintype "bidirectional"))
      (node (ref "U3") (pin "20") (pinfunction "VCC_20") (pintype "power_in"))
    )
    (net (code "4") (name "5V_IN") (class "Default")
      (node (ref "U$7") (pin "VCC") (pinfunction "VCC_VCC") (pintype "bidirectional"))
      (node (ref "U$7") (pin "VCC1") (pinfunction "VCC_VCC1") (pintype "bidirectional"))
    )
    (net (code "5") (name "A0") (class "Default")
      (node (ref "U$2") (pin "P85") (pinfunction "IO_L43P_GCLK5_1_P85") (pintype "bidirectional"))
    )
    (net (code "6") (name "A1") (class "Default")
      (node (ref "U$2") (pin "P83") (pinfunction "IO_L45P_1_P83") (pintype "bidirectional"))
    )
    (net (code "7") (name "A2") (class "Default")
      (node (ref "U$2") (pin "P81") (pinfunction "IO_L46P_1_P81") (pintype "bidirectional"))
    )
    (net (code "8") (name "A3") (class "Default")
      (node (ref "U$2") (pin "P79") (pinfunction "IO_L47P_1_P79") (pintype "bidirectional"))
    )
    (net (code "9") (name "A4") (class "Default")
      (node (ref "U$2") (pin "P80") (pinfunction "IO_L46N_1_P80") (pintype "bidirectional"))
    )
    (net (code "10") (name "A5") (class "Default")
      (node (ref "U$2") (pin "P82") (pinfunction "IO_L45N_1_P82") (pintype "bidirectional"))
    )
    (net (code "11") (name "A6") (class "Default")
      (node (ref "U$2") (pin "P84") (pinfunction "IO_L43N_GCLK4_1_P84") (pintype "bidirectional"))
    )
    (net (code "12") (name "A7") (class "Default")
      (node (ref "U$2") (pin "P87") (pinfunction "IO_L42N_GCLK6_TRDY1_1_P87") (pintype "bidirectional"))
    )
    (net (code "13") (name "A8") (class "Default")
      (node (ref "U$2") (pin "P92") (pinfunction "IO_L41N_GCLK8_1_P92") (pintype "bidirectional"))
    )
    (net (code "14") (name "A9") (class "Default")
      (node (ref "U$2") (pin "P94") (pinfunction "IO_L40N_GCLK10_1_P94") (pintype "bidirectional"))
    )
    (net (code "15") (name "A10") (class "Default")
      (node (ref "U$2") (pin "P88") (pinfunction "IO_L42P_GCLK7_1_P88") (pintype "bidirectional"))
    )
    (net (code "16") (name "A11") (class "Default")
      (node (ref "U$2") (pin "P97") (pinfunction "IO_L34N_1_P97") (pintype "bidirectional"))
    )
    (net (code "17") (name "A12") (class "Default")
      (node (ref "U$2") (pin "P99") (pinfunction "IO_L33N_1_P99") (pintype "bidirectional"))
    )
    (net (code "18") (name "AUDIO") (class "Default")
      (node (ref "J1") (pin "2") (pinfunction "RING_2") (pintype "passive"))
      (node (ref "J1") (pin "5") (pinfunction "TIP_5") (pintype "passive"))
      (node (ref "R10") (pin "2") (pinfunction "2_2") (pintype "passive"))
      (node (ref "R11") (pin "2") (pinfunction "2_2") (pintype "passive"))
      (node (ref "R12") (pin "2") (pinfunction "2_2") (pintype "passive"))
      (node (ref "R13") (pin "2") (pinfunction "2_2") (pintype "passive"))
      (node (ref "R14") (pin "2") (pinfunction "2_2") (pintype "passive"))
      (node (ref "R16") (pin "2") (pinfunction "2_2") (pintype "passive"))
      (node (ref "R17") (pin "2") (pinfunction "2_2") (pintype "passive"))
      (node (ref "R18") (pin "2") (pinfunction "2_2") (pintype "passive"))
      (node (ref "R19") (pin "2") (pinfunction "2_2") (pintype "passive"))
      (node (ref "R20") (pin "2") (pinfunction "2_2") (pintype "passive"))
      (node (ref "R21") (pin "2") (pinfunction "2_2") (pintype "passive"))
      (node (ref "R22") (pin "2") (pinfunction "2_2") (pintype "passive"))
      (node (ref "R25") (pin "2") (pinfunction "2_2") (pintype "passive"))
      (node (ref "R26") (pin "2") (pinfunction "2_2") (pintype "passive"))
      (node (ref "R3") (pin "2") (pinfunction "2_2") (pintype "passive"))
      (node (ref "R9") (pin "2") (pinfunction "2_2") (pintype "passive"))
    )
    (net (code "19") (name "BA0") (class "Default")
      (node (ref "U$2") (pin "P95") (pinfunction "IO_L40P_GCLK11_1_P95") (pintype "bidirectional"))
    )
    (net (code "20") (name "BA1") (class "Default")
      (node (ref "U$2") (pin "P93") (pinfunction "IO_L41P_GCLK9_IRDY1_1_P93") (pintype "bidirectional"))
    )
    (net (code "21") (name "BTN0") (class "Default")
      (node (ref "R27") (pin "1") (pinfunction "1_1") (pintype "passive"))
      (node (ref "S1") (pin "3") (pinfunction "3_3") (pintype "passive"))
      (node (ref "S1") (pin "4") (pinfunction "4_4") (pintype "passive"))
      (node (ref "U$2") (pin "P144") (pinfunction "IO_L1P_HSWAPEN_0_P144") (pintype "bidirectional"))
    )
    (net (code "22") (name "BTN1") (class "Default")
      (node (ref "R28") (pin "1") (pinfunction "1_1") (pintype "passive"))
      (node (ref "S2") (pin "3") (pinfunction "3_3") (pintype "passive"))
      (node (ref "S2") (pin "4") (pinfunction "4_4") (pintype "passive"))
      (node (ref "U$2") (pin "P143") (pinfunction "IO_L1N_VREF_0_P143") (pintype "bidirectional"))
    )
    (net (code "23") (name "BTN2") (class "Default")
      (node (ref "R29") (pin "1") (pinfunction "1_1") (pintype "passive"))
      (node (ref "S3") (pin "3") (pinfunction "3_3") (pintype "passive"))
      (node (ref "S3") (pin "4") (pinfunction "4_4") (pintype "passive"))
      (node (ref "U$2") (pin "P142") (pinfunction "IO_L2P_0_P142") (pintype "bidirectional"))
    )
    (net (code "24") (name "BTN3") (class "Default")
      (node (ref "R30") (pin "1") (pinfunction "1_1") (pintype "passive"))
      (node (ref "S4") (pin "3") (pinfunction "3_3") (pintype "passive"))
      (node (ref "S4") (pin "4") (pinfunction "4_4") (pintype "passive"))
      (node (ref "U$2") (pin "P141") (pinfunction "IO_L2N_0_P141") (pintype "bidirectional"))
    )
    (net (code "25") (name "BTN4") (class "Default")
      (node (ref "R31") (pin "1") (pinfunction "1_1") (pintype "passive"))
      (node (ref "S5") (pin "3") (pinfunction "3_3") (pintype "passive"))
      (node (ref "S5") (pin "4") (pinfunction "4_4") (pintype "passive"))
      (node (ref "U$2") (pin "P140") (pinfunction "IO_L3P_0_P140") (pintype "bidirectional"))
    )
    (net (code "26") (name "BTN5") (class "Default")
      (node (ref "R32") (pin "1") (pinfunction "1_1") (pintype "passive"))
      (node (ref "S6") (pin "3") (pinfunction "3_3") (pintype "passive"))
      (node (ref "S6") (pin "4") (pinfunction "4_4") (pintype "passive"))
      (node (ref "U$2") (pin "P139") (pinfunction "IO_L3N_0_P139") (pintype "bidirectional"))
    )
    (net (code "27") (name "BTN6") (class "Default")
      (node (ref "R33") (pin "1") (pinfunction "1_1") (pintype "passive"))
      (node (ref "S7") (pin "3") (pinfunction "3_3") (pintype "passive"))
      (node (ref "S7") (pin "4") (pinfunction "4_4") (pintype "passive"))
      (node (ref "U$2") (pin "P138") (pinfunction "IO_L4P_0_P138") (pintype "bidirectional"))
    )
    (net (code "28") (name "BTN7") (class "Default")
      (node (ref "R34") (pin "1") (pinfunction "1_1") (pintype "passive"))
      (node (ref "S8") (pin "3") (pinfunction "3_3") (pintype "passive"))
      (node (ref "S8") (pin "4") (pinfunction "4_4") (pintype "passive"))
      (node (ref "U$2") (pin "P137") (pinfunction "IO_L4N_0_P137") (pintype "bidirectional"))
    )
    (net (code "29") (name "BTN8") (class "Default")
      (node (ref "R35") (pin "1") (pinfunction "1_1") (pintype "passive"))
      (node (ref "S9") (pin "3") (pinfunction "3_3") (pintype "passive"))
      (node (ref "S9") (pin "4") (pinfunction "4_4") (pintype "passive"))
      (node (ref "U$2") (pin "P134") (pinfunction "IO_L34P_GCLK19_0_P134") (pintype "bidirectional"))
    )
    (net (code "30") (name "BTN9") (class "Default")
      (node (ref "R36") (pin "1") (pinfunction "1_1") (pintype "passive"))
      (node (ref "S10") (pin "3") (pinfunction "3_3") (pintype "passive"))
      (node (ref "S10") (pin "4") (pinfunction "4_4") (pintype "passive"))
      (node (ref "U$2") (pin "P133") (pinfunction "IO_L34N_GCLK18_0_P133") (pintype "bidirectional"))
    )
    (net (code "31") (name "BTN10") (class "Default")
      (node (ref "R37") (pin "1") (pinfunction "1_1") (pintype "passive"))
      (node (ref "S11") (pin "3") (pinfunction "3_3") (pintype "passive"))
      (node (ref "S11") (pin "4") (pinfunction "4_4") (pintype "passive"))
      (node (ref "U$2") (pin "P132") (pinfunction "IO_L35P_GCLK17_0_P132") (pintype "bidirectional"))
    )
    (net (code "32") (name "BTN11") (class "Default")
      (node (ref "R38") (pin "1") (pinfunction "1_1") (pintype "passive"))
      (node (ref "S12") (pin "3") (pinfunction "3_3") (pintype "passive"))
      (node (ref "S12") (pin "4") (pinfunction "4_4") (pintype "passive"))
      (node (ref "U$2") (pin "P131") (pinfunction "IO_L35N_GCLK16_0_P131") (pintype "bidirectional"))
    )
    (net (code "33") (name "CAS") (class "Default")
      (node (ref "U$2") (pin "P102") (pinfunction "IO_L32P_1_P102") (pintype "bidirectional"))
    )
    (net (code "34") (name "CCLK") (class "Default")
      (node (ref "U$2") (pin "P70") (pinfunction "IO_L1P_CCLK_2_P70") (pintype "bidirectional"))
      (node (ref "U1") (pin "6") (pinfunction "CLK_6") (pintype "input"))
    )
    (net (code "35") (name "CKE_RAM") (class "Default")
      (node (ref "U$2") (pin "P101") (pinfunction "IO_L32N_1_P101") (pintype "bidirectional"))
    )
    (net (code "36") (name "CLK_NES") (class "Default")
      (node (ref "U$3") (pin "CLOCK") (pinfunction "CLOCK_CLOCK") (pintype "bidirectional"))
      (node (ref "U3") (pin "2") (pinfunction "A1_2") (pintype "bidirectional"))
    )
    (net (code "37") (name "CLK_NES_FPGA") (class "Default")
      (node (ref "U$2") (pin "P48") (pinfunction "IO_L48P_D7_2_P48") (pintype "bidirectional"))
      (node (ref "U3") (pin "18") (pinfunction "B1_18") (pintype "bidirectional"))
    )
    (net (code "38") (name "CS") (class "Default")
      (node (ref "U$2") (pin "P98") (pinfunction "IO_L34P_1_P98") (pintype "bidirectional"))
    )
    (net (code "39") (name "DATA_NES") (class "Default")
      (node (ref "U$3") (pin "DATA") (pinfunction "DATA_DATA") (pintype "bidirectional"))
      (node (ref "U2") (pin "2") (pinfunction "A1_2") (pintype "bidirectional"))
    )
    (net (code "40") (name "DATA_NES_FPGA") (class "Default")
      (node (ref "U$2") (pin "P56") (pinfunction "IO_L30P_GCLK1_D13_2_P56") (pintype "bidirectional"))
      (node (ref "U2") (pin "18") (pinfunction "B1_18") (pintype "bidirectional"))
    )
    (net (code "41") (name "DBG0") (class "Default")
      (node (ref "LED3") (pin "A") (pinfunction "A_A") (pintype "passive"))
      (node (ref "R39") (pin "1") (pinfunction "1_1") (pintype "passive"))
      (node (ref "U$2") (pin "P24") (pinfunction "IO_L41P_GCLK27_3_P24") (pintype "bidirectional"))
    )
    (net (code "42") (name "DBG1") (class "Default")
      (node (ref "LED4") (pin "A") (pinfunction "A_A") (pintype "passive"))
      (node (ref "R40") (pin "1") (pinfunction "1_1") (pintype "passive"))
      (node (ref "U$2") (pin "P26") (pinfunction "IO_L37N_3_P26") (pintype "bidirectional"))
    )
    (net (code "43") (name "DBG2") (class "Default")
      (node (ref "LED5") (pin "A") (pinfunction "A_A") (pintype "passive"))
      (node (ref "R41") (pin "1") (pinfunction "1_1") (pintype "passive"))
      (node (ref "U$2") (pin "P27") (pinfunction "IO_L37P_3_P27") (pintype "bidirectional"))
    )
    (net (code "44") (name "DBG3") (class "Default")
      (node (ref "LED6") (pin "A") (pinfunction "A_A") (pintype "passive"))
      (node (ref "R42") (pin "1") (pinfunction "1_1") (pintype "passive"))
      (node (ref "U$2") (pin "P29") (pinfunction "IO_L36N_3_P29") (pintype "bidirectional"))
    )
    (net (code "45") (name "DBG4") (class "Default")
      (node (ref "LED7") (pin "A") (pinfunction "A_A") (pintype "passive"))
      (node (ref "R43") (pin "1") (pinfunction "1_1") (pintype "passive"))
      (node (ref "U$2") (pin "P30") (pinfunction "IO_L36P_3_P30") (pintype "bidirectional"))
    )
    (net (code "46") (name "DBG5") (class "Default")
      (node (ref "LED8") (pin "A") (pinfunction "A_A") (pintype "passive"))
      (node (ref "R44") (pin "1") (pinfunction "1_1") (pintype "passive"))
      (node (ref "U$2") (pin "P32") (pinfunction "IO_L2N_3_P32") (pintype "bidirectional"))
    )
    (net (code "47") (name "DBG6") (class "Default")
      (node (ref "LED15") (pin "A") (pinfunction "A_A") (pintype "passive"))
      (node (ref "R45") (pin "1") (pinfunction "1_1") (pintype "passive"))
      (node (ref "U$2") (pin "P33") (pinfunction "IO_L2P_3_P33") (pintype "bidirectional"))
    )
    (net (code "48") (name "DBG7") (class "Default")
      (node (ref "LED16") (pin "A") (pinfunction "A_A") (pintype "passive"))
      (node (ref "R46") (pin "1") (pinfunction "1_1") (pintype "passive"))
      (node (ref "U$2") (pin "P34") (pinfunction "IO_L1N_VREF_3_P34") (pintype "bidirectional"))
    )
    (net (code "49") (name "DBG8") (class "Default")
      (node (ref "LED9") (pin "A") (pinfunction "A_A") (pintype "passive"))
      (node (ref "R47") (pin "1") (pinfunction "1_1") (pintype "passive"))
      (node (ref "U$2") (pin "P35") (pinfunction "IO_L1P_3_P35") (pintype "bidirectional"))
    )
    (net (code "50") (name "DBG9") (class "Default")
      (node (ref "LED10") (pin "A") (pinfunction "A_A") (pintype "passive"))
      (node (ref "R48") (pin "1") (pinfunction "1_1") (pintype "passive"))
      (node (ref "U$2") (pin "P40") (pinfunction "IO_L64N_D9_2_P40") (pintype "bidirectional"))
    )
    (net (code "51") (name "DBG10") (class "Default")
      (node (ref "LED11") (pin "A") (pinfunction "A_A") (pintype "passive"))
      (node (ref "R49") (pin "1") (pinfunction "1_1") (pintype "passive"))
      (node (ref "U$2") (pin "P41") (pinfunction "IO_L64P_D8_2_P41") (pintype "bidirectional"))
    )
    (net (code "52") (name "DBG11") (class "Default")
      (node (ref "LED12") (pin "A") (pinfunction "A_A") (pintype "passive"))
      (node (ref "R50") (pin "1") (pinfunction "1_1") (pintype "passive"))
      (node (ref "U$2") (pin "P43") (pinfunction "IO_L62N_D6_2_P43") (pintype "bidirectional"))
    )
    (net (code "53") (name "DBG12") (class "Default")
      (node (ref "LED13") (pin "A") (pinfunction "A_A") (pintype "passive"))
      (node (ref "R51") (pin "1") (pinfunction "1_1") (pintype "passive"))
      (node (ref "U$2") (pin "P44") (pinfunction "IO_L62P_D5_2_P44") (pintype "bidirectional"))
    )
    (net (code "54") (name "DBG13") (class "Default")
      (node (ref "LED14") (pin "A") (pinfunction "A_A") (pintype "passive"))
      (node (ref "R52") (pin "1") (pinfunction "1_1") (pintype "passive"))
      (node (ref "U$2") (pin "P45") (pinfunction "IO_L49N_D4_2_P45") (pintype "bidirectional"))
    )
    (net (code "55") (name "DBG14") (class "Default")
      (node (ref "LED17") (pin "A") (pinfunction "A_A") (pintype "passive"))
      (node (ref "R53") (pin "1") (pinfunction "1_1") (pintype "passive"))
      (node (ref "U$2") (pin "P46") (pinfunction "IO_L49P_D3_2_P46") (pintype "bidirectional"))
    )
    (net (code "56") (name "DBG15") (class "Default")
      (node (ref "LED18") (pin "A") (pinfunction "A_A") (pintype "passive"))
      (node (ref "R54") (pin "1") (pinfunction "1_1") (pintype "passive"))
      (node (ref "U$2") (pin "P47") (pinfunction "IO_L48N_RDWR_B_VREF_2_P47") (pintype "bidirectional"))
    )
    (net (code "57") (name "FET0") (class "Default")
      (node (ref "IC1") (pin "1") (pinfunction "G_1") (pintype "bidirectional"))
      (node (ref "U$2") (pin "P2") (pinfunction "IO_L83P_3_P2") (pintype "bidirectional"))
    )
    (net (code "58") (name "FET1") (class "Default")
      (node (ref "IC2") (pin "1") (pinfunction "G_1") (pintype "bidirectional"))
      (node (ref "U$2") (pin "P5") (pinfunction "IO_L52N_3_P5") (pintype "bidirectional"))
    )
    (net (code "59") (name "FET2") (class "Default")
      (node (ref "IC3") (pin "1") (pinfunction "G_1") (pintype "bidirectional"))
      (node (ref "U$2") (pin "P6") (pinfunction "IO_L52P_3_P6") (pintype "bidirectional"))
    )
    (net (code "60") (name "FET3") (class "Default")
      (node (ref "IC4") (pin "1") (pinfunction "G_1") (pintype "bidirectional"))
      (node (ref "U$2") (pin "P7") (pinfunction "IO_L51N_3_P7") (pintype "bidirectional"))
    )
    (net (code "61") (name "FET4") (class "Default")
      (node (ref "IC5") (pin "1") (pinfunction "G_1") (pintype "bidirectional"))
      (node (ref "U$2") (pin "P8") (pinfunction "IO_L51P_3_P8") (pintype "bidirectional"))
    )
    (net (code "62") (name "FET5") (class "Default")
      (node (ref "IC6") (pin "1") (pinfunction "G_1") (pintype "bidirectional"))
      (node (ref "U$2") (pin "P9") (pinfunction "IO_L50N_3_P9") (pintype "bidirectional"))
    )
    (net (code "63") (name "FET6") (class "Default")
      (node (ref "IC7") (pin "1") (pinfunction "G_1") (pintype "bidirectional"))
      (node (ref "U$2") (pin "P10") (pinfunction "IO_L50P_3_P10") (pintype "bidirectional"))
    )
    (net (code "64") (name "FET7") (class "Default")
      (node (ref "IC8") (pin "1") (pinfunction "G_1") (pintype "bidirectional"))
      (node (ref "U$2") (pin "P11") (pinfunction "IO_L49N_3_P11") (pintype "bidirectional"))
    )
    (net (code "65") (name "FET8") (class "Default")
      (node (ref "IC9") (pin "1") (pinfunction "G_1") (pintype "bidirectional"))
      (node (ref "U$2") (pin "P12") (pinfunction "IO_L49P_3_P12") (pintype "bidirectional"))
    )
    (net (code "66") (name "FET9") (class "Default")
      (node (ref "IC10") (pin "1") (pinfunction "G_1") (pintype "bidirectional"))
      (node (ref "U$2") (pin "P14") (pinfunction "IO_L44N_GCLK20_3_P14") (pintype "bidirectional"))
    )
    (net (code "67") (name "FET10") (class "Default")
      (node (ref "IC11") (pin "1") (pinfunction "G_1") (pintype "bidirectional"))
      (node (ref "U$2") (pin "P15") (pinfunction "IO_L44P_GCLK21_3_P15") (pintype "bidirectional"))
    )
    (net (code "68") (name "FET11") (class "Default")
      (node (ref "IC12") (pin "1") (pinfunction "G_1") (pintype "bidirectional"))
      (node (ref "U$2") (pin "P16") (pinfunction "IO_L43N_GCLK22_IRDY2_3_P16") (pintype "bidirectional"))
    )
    (net (code "69") (name "FET12") (class "Default")
      (node (ref "IC13") (pin "1") (pinfunction "G_1") (pintype "bidirectional"))
      (node (ref "U$2") (pin "P17") (pinfunction "IO_L43P_GCLK23_3_P17") (pintype "bidirectional"))
    )
    (net (code "70") (name "FET13") (class "Default")
      (node (ref "IC14") (pin "1") (pinfunction "G_1") (pintype "bidirectional"))
      (node (ref "U$2") (pin "P21") (pinfunction "IO_L42N_GCLK24_3_P21") (pintype "bidirectional"))
    )
    (net (code "71") (name "FET14") (class "Default")
      (node (ref "IC15") (pin "1") (pinfunction "G_1") (pintype "bidirectional"))
      (node (ref "U$2") (pin "P22") (pinfunction "IO_L42P_GCLK25_TRDY2_3_P22") (pintype "bidirectional"))
    )
    (net (code "72") (name "FET15") (class "Default")
      (node (ref "IC16") (pin "1") (pinfunction "G_1") (pintype "bidirectional"))
      (node (ref "U$2") (pin "P23") (pinfunction "IO_L41N_GCLK26_3_P23") (pintype "bidirectional"))
    )
    (net (code "73") (name "FLASH_CS") (class "Default")
      (node (ref "R5") (pin "1") (pinfunction "1_1") (pintype "passive"))
      (node (ref "U$2") (pin "P38") (pinfunction "IO_L65N_CSO_B_2_P38") (pintype "bidirectional"))
      (node (ref "U1") (pin "1") (pinfunction "~{CS}_1") (pintype "input"))
    )
    (net (code "74") (name "FLASH_D0") (class "Default")
      (node (ref "U$2") (pin "P64") (pinfunction "IO_L3N_MOSI_CSI_B_MISO0_2_P64") (pintype "bidirectional"))
      (node (ref "U1") (pin "5") (pinfunction "DI(IO0)_5") (pintype "bidirectional"))
    )
    (net (code "75") (name "FLASH_D1") (class "Default")
      (node (ref "U$2") (pin "P65") (pinfunction "IO_L3P_D0_DIN_MISO_MISO1_2_P65") (pintype "bidirectional"))
      (node (ref "U1") (pin "2") (pinfunction "DO(IO1)_2") (pintype "bidirectional"))
    )
    (net (code "76") (name "FLASH_D2") (class "Default")
      (node (ref "R6") (pin "2") (pinfunction "2_2") (pintype "passive"))
      (node (ref "U$2") (pin "P62") (pinfunction "IO_L12P_D1_MISO2_2_P62") (pintype "bidirectional"))
      (node (ref "U1") (pin "3") (pinfunction "~{WP}(IO2)_3") (pintype "bidirectional"))
    )
    (net (code "77") (name "FLASH_D3") (class "Default")
      (node (ref "R7") (pin "2") (pinfunction "2_2") (pintype "passive"))
      (node (ref "U$2") (pin "P61") (pinfunction "IO_L12N_D2_MISO3_2_P61") (pintype "bidirectional"))
      (node (ref "U1") (pin "7") (pinfunction "~{HOLD}(IO3)_7") (pintype "bidirectional"))
    )
    (net (code "78") (name "G0") (class "Default")
      (node (ref "U$2") (pin "P57") (pinfunction "IO_L14N_D12_2_P57") (pintype "bidirectional"))
    )
    (net (code "79") (name "G1") (class "Default")
      (node (ref "U$2") (pin "P51") (pinfunction "IO_L31P_GCLK31_D14_2_P51") (pintype "bidirectional"))
    )
    (net (code "80") (name "GND") (class "Default")
      (node (ref "C1") (pin "2") (pinfunction "2_2") (pintype "passive"))
      (node (ref "C10") (pin "2") (pinfunction "2_2") (pintype "passive"))
      (node (ref "C11") (pin "2") (pinfunction "2_2") (pintype "passive"))
      (node (ref "C12") (pin "2") (pinfunction "2_2") (pintype "passive"))
      (node (ref "C13") (pin "2") (pinfunction "2_2") (pintype "passive"))
      (node (ref "C14") (pin "2") (pinfunction "2_2") (pintype "passive"))
      (node (ref "C15") (pin "2") (pinfunction "2_2") (pintype "passive"))
      (node (ref "C16") (pin "2") (pinfunction "2_2") (pintype "passive"))
      (node (ref "C17") (pin "2") (pinfunction "2_2") (pintype "passive"))
      (node (ref "C18") (pin "2") (pinfunction "2_2") (pintype "passive"))
      (node (ref "C19") (pin "2") (pinfunction "2_2") (pintype "passive"))
      (node (ref "C2") (pin "2") (pinfunction "2_2") (pintype "passive"))
      (node (ref "C22") (pin "2") (pinfunction "2_2") (pintype "passive"))
      (node (ref "C23") (pin "2") (pinfunction "2_2") (pintype "passive"))
      (node (ref "C24") (pin "2") (pinfunction "2_2") (pintype "passive"))
      (node (ref "C25") (pin "2") (pinfunction "2_2") (pintype "passive"))
      (node (ref "C26") (pin "2") (pinfunction "-_2") (pintype "bidirectional"))
      (node (ref "C27") (pin "2") (pinfunction "-_2") (pintype "bidirectional"))
      (node (ref "C3") (pin "2") (pinfunction "2_2") (pintype "passive"))
      (node (ref "C32") (pin "2") (pinfunction "2_2") (pintype "passive"))
      (node (ref "C33") (pin "2") (pinfunction "2_2") (pintype "passive"))
      (node (ref "C34") (pin "2") (pinfunction "2_2") (pintype "passive"))
      (node (ref "C4") (pin "2") (pinfunction "2_2") (pintype "passive"))
      (node (ref "C5") (pin "2") (pinfunction "2_2") (pintype "passive"))
      (node (ref "C6") (pin "2") (pinfunction "2_2") (pintype "passive"))
      (node (ref "C7") (pin "2") (pinfunction "2_2") (pintype "passive"))
      (node (ref "C8") (pin "2") (pinfunction "2_2") (pintype "passive"))
      (node (ref "C9") (pin "2") (pinfunction "2_2") (pintype "passive"))
      (node (ref "IC17") (pin "1") (pinfunction "GROUND/ADJUST_1") (pintype "bidirectional"))
      (node (ref "IC18") (pin "1") (pinfunction "GROUND/ADJUST_1") (pintype "bidirectional"))
      (node (ref "J1") (pin "1") (pinfunction "SLEEVE_1") (pintype "passive"))
      (node (ref "LED1") (pin "C") (pinfunction "C_C") (pintype "passive"))
      (node (ref "LED10") (pin "C") (pinfunction "C_C") (pintype "passive"))
      (node (ref "LED11") (pin "C") (pinfunction "C_C") (pintype "passive"))
      (node (ref "LED12") (pin "C") (pinfunction "C_C") (pintype "passive"))
      (node (ref "LED13") (pin "C") (pinfunction "C_C") (pintype "passive"))
      (node (ref "LED14") (pin "C") (pinfunction "C_C") (pintype "passive"))
      (node (ref "LED15") (pin "C") (pinfunction "C_C") (pintype "passive"))
      (node (ref "LED16") (pin "C") (pinfunction "C_C") (pintype "passive"))
      (node (ref "LED17") (pin "C") (pinfunction "C_C") (pintype "passive"))
      (node (ref "LED18") (pin "C") (pinfunction "C_C") (pintype "passive"))
      (node (ref "LED2") (pin "C") (pinfunction "C_C") (pintype "passive"))
      (node (ref "LED3") (pin "C") (pinfunction "C_C") (pintype "passive"))
      (node (ref "LED4") (pin "C") (pinfunction "C_C") (pintype "passive"))
      (node (ref "LED5") (pin "C") (pinfunction "C_C") (pintype "passive"))
      (node (ref "LED6") (pin "C") (pinfunction "C_C") (pintype "passive"))
      (node (ref "LED7") (pin "C") (pinfunction "C_C") (pintype "passive"))
      (node (ref "LED8") (pin "C") (pinfunction "C_C") (pintype "passive"))
      (node (ref "LED9") (pin "C") (pinfunction "C_C") (pintype "passive"))
      (node (ref "R23") (pin "2") (pinfunction "2_2") (pintype "passive"))
      (node (ref "R24") (pin "2") (pinfunction "2_2") (pintype "passive"))
      (node (ref "S1") (pin "1") (pinfunction "1_1") (pintype "passive"))
      (node (ref "S1") (pin "2") (pinfunction "2_2") (pintype "passive"))
      (node (ref "S10") (pin "1") (pinfunction "1_1") (pintype "passive"))
      (node (ref "S10") (pin "2") (pinfunction "2_2") (pintype "passive"))
      (node (ref "S11") (pin "1") (pinfunction "1_1") (pintype "passive"))
      (node (ref "S11") (pin "2") (pinfunction "2_2") (pintype "passive"))
      (node (ref "S12") (pin "1") (pinfunction "1_1") (pintype "passive"))
      (node (ref "S12") (pin "2") (pinfunction "2_2") (pintype "passive"))
      (node (ref "S2") (pin "1") (pinfunction "1_1") (pintype "passive"))
      (node (ref "S2") (pin "2") (pinfunction "2_2") (pintype "passive"))
      (node (ref "S3") (pin "1") (pinfunction "1_1") (pintype "passive"))
      (node (ref "S3") (pin "2") (pinfunction "2_2") (pintype "passive"))
      (node (ref "S4") (pin "1") (pinfunction "1_1") (pintype "passive"))
      (node (ref "S4") (pin "2") (pinfunction "2_2") (pintype "passive"))
      (node (ref "S5") (pin "1") (pinfunction "1_1") (pintype "passive"))
      (node (ref "S5") (pin "2") (pinfunction "2_2") (pintype "passive"))
      (node (ref "S6") (pin "1") (pinfunction "1_1") (pintype "passive"))
      (node (ref "S6") (pin "2") (pinfunction "2_2") (pintype "passive"))
      (node (ref "S7") (pin "1") (pinfunction "1_1") (pintype "passive"))
      (node (ref "S7") (pin "2") (pinfunction "2_2") (pintype "passive"))
      (node (ref "S8") (pin "1") (pinfunction "1_1") (pintype "passive"))
      (node (ref "S8") (pin "2") (pinfunction "2_2") (pintype "passive"))
      (node (ref "S9") (pin "1") (pinfunction "1_1") (pintype "passive"))
      (node (ref "S9") (pin "2") (pinfunction "2_2") (pintype "passive"))
      (node (ref "U$1") (pin "2") (pinfunction "GND_2") (pintype "bidirectional"))
      (node (ref "U$2") (pin "P108") (pinfunction "GND_P108") (pintype "bidirectional"))
      (node (ref "U$2") (pin "P113") (pinfunction "GND_P113") (pintype "bidirectional"))
      (node (ref "U$2") (pin "P13") (pinfunction "GND_P13") (pintype "bidirectional"))
      (node (ref "U$2") (pin "P130") (pinfunction "GND_P130") (pintype "bidirectional"))
      (node (ref "U$2") (pin "P136") (pinfunction "GND_P136") (pintype "bidirectional"))
      (node (ref "U$2") (pin "P25") (pinfunction "GND_P25") (pintype "bidirectional"))
      (node (ref "U$2") (pin "P3") (pinfunction "GND_P3") (pintype "bidirectional"))
      (node (ref "U$2") (pin "P49") (pinfunction "GND_P49") (pintype "bidirectional"))
      (node (ref "U$2") (pin "P54") (pinfunction "GND_P54") (pintype "bidirectional"))
      (node (ref "U$2") (pin "P60") (pinfunction "IO_L13P_M1_2_P60") (pintype "bidirectional"))
      (node (ref "U$2") (pin "P68") (pinfunction "GND_P68") (pintype "bidirectional"))
      (node (ref "U$2") (pin "P73") (pinfunction "SUSPEND_P73") (pintype "bidirectional"))
      (node (ref "U$2") (pin "P77") (pinfunction "GND_P77") (pintype "bidirectional"))
      (node (ref "U$2") (pin "P91") (pinfunction "GND_P91") (pintype "bidirectional"))
      (node (ref "U$2") (pin "P96") (pinfunction "GND_P96") (pintype "bidirectional"))
      (node (ref "U$3") (pin "GND") (pinfunction "GND_GND") (pintype "bidirectional"))
      (node (ref "U$7") (pin "GND") (pinfunction "GND_GND") (pintype "bidirectional"))
      (node (ref "U$7") (pin "GND1") (pinfunction "GND_GND1") (pintype "bidirectional"))
      (node (ref "U$7") (pin "P$10") (pinfunction "GND_P$10") (pintype "bidirectional"))
      (node (ref "U$7") (pin "P$7") (pinfunction "GND_P$7") (pintype "bidirectional"))
      (node (ref "U$7") (pin "P$8") (pinfunction "GND_P$8") (pintype "bidirectional"))
      (node (ref "U$7") (pin "P$9") (pinfunction "GND_P$9") (pintype "bidirectional"))
      (node (ref "U1") (pin "4") (pinfunction "GND_4") (pintype "power_in"))
      (node (ref "U2") (pin "10") (pinfunction "GND_10") (pintype "passive"))
      (node (ref "U2") (pin "11") (pinfunction "B8_11") (pintype "bidirectional"))
      (node (ref "U2") (pin "19") (pinfunction "~{OE}_19") (pintype "input"))
      (node (ref "U3") (pin "1") (pinfunction "DIR_1") (pintype "input"))
      (node (ref "U3") (pin "10") (pinfunction "GND_10") (pintype "passive"))
      (node (ref "U3") (pin "11") (pinfunction "B8_11") (pintype "bidirectional"))
      (node (ref "U3") (pin "12") (pinfunction "B7_12") (pintype "bidirectional"))
      (node (ref "U3") (pin "13") (pinfunction "B6_13") (pintype "bidirectional"))
      (node (ref "U3") (pin "14") (pinfunction "B5_14") (pintype "bidirectional"))
      (node (ref "U3") (pin "15") (pinfunction "B4_15") (pintype "bidirectional"))
      (node (ref "U3") (pin "16") (pinfunction "B3_16") (pintype "bidirectional"))
      (node (ref "U3") (pin "19") (pinfunction "~{OE}_19") (pintype "input"))
    )
    (net (code "81") (name "LATCH_NES") (class "Default")
      (node (ref "U$3") (pin "LATCH") (pinfunction "LATCH_LATCH") (pintype "bidirectional"))
      (node (ref "U3") (pin "3") (pinfunction "A2_3") (pintype "bidirectional"))
    )
    (net (code "82") (name "LATCH_NES_FPGA") (class "Default")
      (node (ref "U$2") (pin "P50") (pinfunction "IO_L31N_GCLK30_D15_2_P50") (pintype "bidirectional"))
      (node (ref "U3") (pin "17") (pinfunction "B2_17") (pintype "bidirectional"))
    )
    (net (code "83") (name "MISO{slash}TDO") (class "Default")
      (node (ref "U$2") (pin "P106") (pinfunction "TDO_P106") (pintype "bidirectional"))
    )
    (net (code "84") (name "MOSI{slash}TDI") (class "Default")
      (node (ref "U$2") (pin "P110") (pinfunction "TDI_P110") (pintype "bidirectional"))
    )
    (net (code "85") (name "Net-(C26-+)") (class "Default")
      (node (ref "C26") (pin "1") (pinfunction "+_1") (pintype "bidirectional"))
      (node (ref "IC18") (pin "4") (pinfunction "TAB_(OUTPUT)_4") (pintype "bidirectional"))
    )
    (net (code "86") (name "Net-(C27-+)") (class "Default")
      (node (ref "C27") (pin "1") (pinfunction "+_1") (pintype "bidirectional"))
      (node (ref "IC17") (pin "4") (pinfunction "TAB_(OUTPUT)_4") (pintype "bidirectional"))
    )
    (net (code "87") (name "Net-(D3-PadC)") (class "Default")
      (node (ref "D3") (pin "C") (pinfunction "C_C") (pintype "passive"))
      (node (ref "U$3") (pin "5V") (pinfunction "5V_5V") (pintype "bidirectional"))
    )
    (net (code "88") (name "Net-(IC1-S)") (class "Default")
      (node (ref "IC1") (pin "2") (pinfunction "S_2") (pintype "bidirectional"))
      (node (ref "R3") (pin "1") (pinfunction "1_1") (pintype "passive"))
    )
    (net (code "89") (name "Net-(IC2-S)") (class "Default")
      (node (ref "IC2") (pin "2") (pinfunction "S_2") (pintype "bidirectional"))
      (node (ref "R9") (pin "1") (pinfunction "1_1") (pintype "passive"))
    )
    (net (code "90") (name "Net-(IC3-S)") (class "Default")
      (node (ref "IC3") (pin "2") (pinfunction "S_2") (pintype "bidirectional"))
      (node (ref "R10") (pin "1") (pinfunction "1_1") (pintype "passive"))
    )
    (net (code "91") (name "Net-(IC4-S)") (class "Default")
      (node (ref "IC4") (pin "2") (pinfunction "S_2") (pintype "bidirectional"))
      (node (ref "R11") (pin "1") (pinfunction "1_1") (pintype "passive"))
    )
    (net (code "92") (name "Net-(IC5-S)") (class "Default")
      (node (ref "IC5") (pin "2") (pinfunction "S_2") (pintype "bidirectional"))
      (node (ref "R12") (pin "1") (pinfunction "1_1") (pintype "passive"))
    )
    (net (code "93") (name "Net-(IC6-S)") (class "Default")
      (node (ref "IC6") (pin "2") (pinfunction "S_2") (pintype "bidirectional"))
      (node (ref "R13") (pin "1") (pinfunction "1_1") (pintype "passive"))
    )
    (net (code "94") (name "Net-(IC7-S)") (class "Default")
      (node (ref "IC7") (pin "2") (pinfunction "S_2") (pintype "bidirectional"))
      (node (ref "R14") (pin "1") (pinfunction "1_1") (pintype "passive"))
    )
    (net (code "95") (name "Net-(IC8-S)") (class "Default")
      (node (ref "IC8") (pin "2") (pinfunction "S_2") (pintype "bidirectional"))
      (node (ref "R16") (pin "1") (pinfunction "1_1") (pintype "passive"))
    )
    (net (code "96") (name "Net-(IC9-S)") (class "Default")
      (node (ref "IC9") (pin "2") (pinfunction "S_2") (pintype "bidirectional"))
      (node (ref "R17") (pin "1") (pinfunction "1_1") (pintype "passive"))
    )
    (net (code "97") (name "Net-(IC10-S)") (class "Default")
      (node (ref "IC10") (pin "2") (pinfunction "S_2") (pintype "bidirectional"))
      (node (ref "R18") (pin "1") (pinfunction "1_1") (pintype "passive"))
    )
    (net (code "98") (name "Net-(IC11-S)") (class "Default")
      (node (ref "IC11") (pin "2") (pinfunction "S_2") (pintype "bidirectional"))
      (node (ref "R19") (pin "1") (pinfunction "1_1") (pintype "passive"))
    )
    (net (code "99") (name "Net-(IC12-S)") (class "Default")
      (node (ref "IC12") (pin "2") (pinfunction "S_2") (pintype "bidirectional"))
      (node (ref "R20") (pin "1") (pinfunction "1_1") (pintype "passive"))
    )
    (net (code "100") (name "Net-(IC13-S)") (class "Default")
      (node (ref "IC13") (pin "2") (pinfunction "S_2") (pintype "bidirectional"))
      (node (ref "R21") (pin "1") (pinfunction "1_1") (pintype "passive"))
    )
    (net (code "101") (name "Net-(IC14-S)") (class "Default")
      (node (ref "IC14") (pin "2") (pinfunction "S_2") (pintype "bidirectional"))
      (node (ref "R22") (pin "1") (pinfunction "1_1") (pintype "passive"))
    )
    (net (code "102") (name "Net-(IC15-S)") (class "Default")
      (node (ref "IC15") (pin "2") (pinfunction "S_2") (pintype "bidirectional"))
      (node (ref "R25") (pin "1") (pinfunction "1_1") (pintype "passive"))
    )
    (net (code "103") (name "Net-(IC16-S)") (class "Default")
      (node (ref "IC16") (pin "2") (pinfunction "S_2") (pintype "bidirectional"))
      (node (ref "R26") (pin "1") (pinfunction "1_1") (pintype "passive"))
    )
    (net (code "104") (name "Net-(R23-Pad1)") (class "Default")
      (node (ref "R23") (pin "1") (pinfunction "1_1") (pintype "passive"))
      (node (ref "U$7") (pin "CC1") (pinfunction "CC1_CC1") (pintype "bidirectional"))
    )
    (net (code "105") (name "Net-(R24-Pad1)") (class "Default")
      (node (ref "R24") (pin "1") (pinfunction "1_1") (pintype "passive"))
      (node (ref "U$7") (pin "CC2") (pinfunction "CC2_CC2") (pintype "bidirectional"))
    )
    (net (code "106") (name "Net-(U$1-OUT)") (class "Default")
      (node (ref "R8") (pin "1") (pinfunction "1_1") (pintype "passive"))
      (node (ref "U$1") (pin "3") (pinfunction "OUT_3") (pintype "bidirectional"))
    )
    (net (code "107") (name "Net-(U$2-DONE_2)") (class "Default")
      (node (ref "LED1") (pin "A") (pinfunction "A_A") (pintype "passive"))
      (node (ref "R4") (pin "1") (pinfunction "1_1") (pintype "passive"))
      (node (ref "U$2") (pin "P71") (pinfunction "DONE_2_P71") (pintype "bidirectional"))
    )
    (net (code "108") (name "Net-(U$2-IO_L65P_INIT_B_2)") (class "Default")
      (node (ref "R1") (pin "2") (pinfunction "2_2") (pintype "passive"))
      (node (ref "U$2") (pin "P39") (pinfunction "IO_L65P_INIT_B_2_P39") (pintype "bidirectional"))
    )
    (net (code "109") (name "Net-(U$2-IO_L83N_VREF_3)") (class "Default")
      (node (ref "LED2") (pin "A") (pinfunction "A_A") (pintype "passive"))
      (node (ref "R15") (pin "2") (pinfunction "2_2") (pintype "passive"))
      (node (ref "U$2") (pin "P1") (pinfunction "IO_L83N_VREF_3_P1") (pintype "bidirectional"))
    )
    (net (code "110") (name "Net-(U$2-PROGRAM_B_2)") (class "Default")
      (node (ref "C24") (pin "1") (pinfunction "1_1") (pintype "passive"))
      (node (ref "R2") (pin "2") (pinfunction "2_2") (pintype "passive"))
      (node (ref "U$2") (pin "P37") (pinfunction "PROGRAM_B_2_P37") (pintype "bidirectional"))
    )
    (net (code "111") (name "OSC_OUT") (class "Default")
      (node (ref "R8") (pin "2") (pinfunction "2_2") (pintype "passive"))
      (node (ref "U$2") (pin "P55") (pinfunction "IO_L30N_GCLK0_USERCCLK_2_P55") (pintype "bidirectional"))
    )
    (net (code "112") (name "R0") (class "Default")
      (node (ref "U$2") (pin "P75") (pinfunction "IO_L74P_AWAKE_1_P75") (pintype "bidirectional"))
    )
    (net (code "113") (name "R1") (class "Default")
      (node (ref "U$2") (pin "P74") (pinfunction "IO_L74N_DOUT_BUSY_1_P74") (pintype "bidirectional"))
    )
    (net (code "114") (name "R2") (class "Default")
      (node (ref "U$2") (pin "P67") (pinfunction "IO_L2P_CMPCLK_2_P67") (pintype "bidirectional"))
    )
    (net (code "115") (name "R3") (class "Default")
      (node (ref "U$2") (pin "P66") (pinfunction "IO_L2N_CMPMOSI_2_P66") (pintype "bidirectional"))
    )
    (net (code "116") (name "R4") (class "Default")
      (node (ref "U$2") (pin "P59") (pinfunction "IO_L13N_D10_2_P59") (pintype "bidirectional"))
    )
    (net (code "117") (name "R5") (class "Default")
      (node (ref "U$2") (pin "P58") (pinfunction "IO_L14P_D11_2_P58") (pintype "bidirectional"))
    )
    (net (code "118") (name "RAS") (class "Default")
      (node (ref "U$2") (pin "P100") (pinfunction "IO_L33P_1_P100") (pintype "bidirectional"))
    )
    (net (code "119") (name "SCK{slash}TCK") (class "Default")
      (node (ref "U$2") (pin "P109") (pinfunction "TCK_P109") (pintype "bidirectional"))
    )
    (net (code "120") (name "SPS") (class "Default")
      (node (ref "U$2") (pin "P78") (pinfunction "IO_L47N_1_P78") (pintype "bidirectional"))
    )
    (net (code "121") (name "SS{slash}TMS") (class "Default")
      (node (ref "U$2") (pin "P107") (pinfunction "TMS_P107") (pintype "bidirectional"))
    )
    (net (code "122") (name "TRM0") (class "Default")
      (node (ref "J10") (pin "1") (pinfunction "1_1") (pintype "passive"))
      (node (ref "U$2") (pin "P127") (pinfunction "IO_L36P_GCLK15_0_P127") (pintype "bidirectional"))
    )
    (net (code "123") (name "TRM1") (class "Default")
      (node (ref "J10") (pin "2") (pinfunction "2_2") (pintype "passive"))
      (node (ref "U$2") (pin "P126") (pinfunction "IO_L36N_GCLK14_0_P126") (pintype "bidirectional"))
    )
    (net (code "124") (name "TRM2") (class "Default")
      (node (ref "J11") (pin "1") (pinfunction "1_1") (pintype "passive"))
      (node (ref "U$2") (pin "P124") (pinfunction "IO_L37P_GCLK13_0_P124") (pintype "bidirectional"))
    )
    (net (code "125") (name "TRM3") (class "Default")
      (node (ref "J11") (pin "2") (pinfunction "2_2") (pintype "passive"))
      (node (ref "U$2") (pin "P123") (pinfunction "IO_L37N_GCLK12_0_P123") (pintype "bidirectional"))
    )
    (net (code "126") (name "TRM4") (class "Default")
      (node (ref "J12") (pin "1") (pinfunction "1_1") (pintype "passive"))
      (node (ref "U$2") (pin "P121") (pinfunction "IO_L62P_0_P121") (pintype "bidirectional"))
    )
    (net (code "127") (name "TRM5") (class "Default")
      (node (ref "J12") (pin "2") (pinfunction "2_2") (pintype "passive"))
      (node (ref "U$2") (pin "P120") (pinfunction "IO_L62N_VREF_0_P120") (pintype "bidirectional"))
    )
    (net (code "128") (name "TRM6") (class "Default")
      (node (ref "J13") (pin "1") (pinfunction "1_1") (pintype "passive"))
      (node (ref "U$2") (pin "P119") (pinfunction "IO_L63P_SCP7_0_P119") (pintype "bidirectional"))
    )
    (net (code "129") (name "TRM7") (class "Default")
      (node (ref "J13") (pin "2") (pinfunction "2_2") (pintype "passive"))
      (node (ref "U$2") (pin "P118") (pinfunction "IO_L63N_SCP6_0_P118") (pintype "bidirectional"))
    )
    (net (code "130") (name "TRM8") (class "Default")
      (node (ref "J14") (pin "1") (pinfunction "1_1") (pintype "passive"))
      (node (ref "U$2") (pin "P117") (pinfunction "IO_L64P_SCP5_0_P117") (pintype "bidirectional"))
    )
    (net (code "131") (name "TRM9") (class "Default")
      (node (ref "J14") (pin "2") (pinfunction "2_2") (pintype "passive"))
      (node (ref "U$2") (pin "P116") (pinfunction "IO_L64N_SCP4_0_P116") (pintype "bidirectional"))
    )
    (net (code "132") (name "TRM10") (class "Default")
      (node (ref "J15") (pin "1") (pinfunction "1_1") (pintype "passive"))
      (node (ref "U$2") (pin "P115") (pinfunction "IO_L65P_SCP3_0_P115") (pintype "bidirectional"))
    )
    (net (code "133") (name "TRM11") (class "Default")
      (node (ref "J15") (pin "2") (pinfunction "2_2") (pintype "passive"))
      (node (ref "U$2") (pin "P114") (pinfunction "IO_L65N_SCP2_0_P114") (pintype "bidirectional"))
    )
    (net (code "134") (name "TRM12") (class "Default")
      (node (ref "J16") (pin "1") (pinfunction "1_1") (pintype "passive"))
      (node (ref "U$2") (pin "P112") (pinfunction "IO_L66P_SCP1_0_P112") (pintype "bidirectional"))
    )
    (net (code "135") (name "TRM13") (class "Default")
      (node (ref "J16") (pin "2") (pinfunction "2_2") (pintype "passive"))
      (node (ref "U$2") (pin "P111") (pinfunction "IO_L66N_SCP0_0_P111") (pintype "bidirectional"))
    )
    (net (code "136") (name "TRM14") (class "Default")
      (node (ref "J17") (pin "1") (pinfunction "1_1") (pintype "passive"))
      (node (ref "U$2") (pin "P105") (pinfunction "IO_L1P_1_P105") (pintype "bidirectional"))
    )
    (net (code "137") (name "TRM15") (class "Default")
      (node (ref "J17") (pin "2") (pinfunction "2_2") (pintype "passive"))
      (node (ref "U$2") (pin "P104") (pinfunction "IO_L1N_VREF_1_P104") (pintype "bidirectional"))
    )
    (net (code "138") (name "unconnected-(IC17-VOUT-Pad2)") (class "Default")
      (node (ref "IC17") (pin "2") (pinfunction "VOUT_2") (pintype "bidirectional"))
    )
    (net (code "139") (name "unconnected-(IC18-VOUT-Pad2)") (class "Default")
      (node (ref "IC18") (pin "2") (pinfunction "VOUT_2") (pintype "bidirectional"))
    )
    (net (code "140") (name "unconnected-(U$2-CMPCS_B_2-PadP72)") (class "Default")
      (node (ref "U$2") (pin "P72") (pinfunction "CMPCS_B_2_P72") (pintype "bidirectional"))
    )
    (net (code "141") (name "unconnected-(U$3-NC-PadN{slash}A)") (class "Default")
      (node (ref "U$3") (pin "N/A") (pinfunction "NC_N/A") (pintype "bidirectional"))
    )
    (net (code "142") (name "unconnected-(U$3-NC2-PadN{slash}A2)") (class "Default")
      (node (ref "U$3") (pin "N/A2") (pinfunction "NC2_N/A2") (pintype "bidirectional"))
    )
    (net (code "143") (name "unconnected-(U2-A2-Pad3)") (class "Default")
      (node (ref "U2") (pin "3") (pinfunction "A2_3") (pintype "bidirectional"))
    )
    (net (code "144") (name "unconnected-(U2-A3-Pad4)") (class "Default")
      (node (ref "U2") (pin "4") (pinfunction "A3_4") (pintype "bidirectional"))
    )
    (net (code "145") (name "unconnected-(U2-A4-Pad5)") (class "Default")
      (node (ref "U2") (pin "5") (pinfunction "A4_5") (pintype "bidirectional"))
    )
    (net (code "146") (name "unconnected-(U2-A5-Pad6)") (class "Default")
      (node (ref "U2") (pin "6") (pinfunction "A5_6") (pintype "bidirectional"))
    )
    (net (code "147") (name "unconnected-(U2-A6-Pad7)") (class "Default")
      (node (ref "U2") (pin "7") (pinfunction "A6_7") (pintype "bidirectional"))
    )
    (net (code "148") (name "unconnected-(U2-A7-Pad8)") (class "Default")
      (node (ref "U2") (pin "8") (pinfunction "A7_8") (pintype "bidirectional"))
    )
    (net (code "149") (name "unconnected-(U2-A8-Pad9)") (class "Default")
      (node (ref "U2") (pin "9") (pinfunction "A8_9") (pintype "bidirectional"))
    )
    (net (code "150") (name "unconnected-(U2-B2-Pad17)") (class "Default")
      (node (ref "U2") (pin "17") (pinfunction "B2_17") (pintype "bidirectional"))
    )
    (net (code "151") (name "unconnected-(U2-B3-Pad16)") (class "Default")
      (node (ref "U2") (pin "16") (pinfunction "B3_16") (pintype "bidirectional"))
    )
    (net (code "152") (name "unconnected-(U2-B4-Pad15)") (class "Default")
      (node (ref "U2") (pin "15") (pinfunction "B4_15") (pintype "bidirectional"))
    )
    (net (code "153") (name "unconnected-(U2-B5-Pad14)") (class "Default")
      (node (ref "U2") (pin "14") (pinfunction "B5_14") (pintype "bidirectional"))
    )
    (net (code "154") (name "unconnected-(U2-B6-Pad13)") (class "Default")
      (node (ref "U2") (pin "13") (pinfunction "B6_13") (pintype "bidirectional"))
    )
    (net (code "155") (name "unconnected-(U2-B7-Pad12)") (class "Default")
      (node (ref "U2") (pin "12") (pinfunction "B7_12") (pintype "bidirectional"))
    )
    (net (code "156") (name "unconnected-(U3-A3-Pad4)") (class "Default")
      (node (ref "U3") (pin "4") (pinfunction "A3_4") (pintype "bidirectional"))
    )
    (net (code "157") (name "unconnected-(U3-A4-Pad5)") (class "Default")
      (node (ref "U3") (pin "5") (pinfunction "A4_5") (pintype "bidirectional"))
    )
    (net (code "158") (name "unconnected-(U3-A5-Pad6)") (class "Default")
      (node (ref "U3") (pin "6") (pinfunction "A5_6") (pintype "bidirectional"))
    )
    (net (code "159") (name "unconnected-(U3-A6-Pad7)") (class "Default")
      (node (ref "U3") (pin "7") (pinfunction "A6_7") (pintype "bidirectional"))
    )
    (net (code "160") (name "unconnected-(U3-A7-Pad8)") (class "Default")
      (node (ref "U3") (pin "8") (pinfunction "A7_8") (pintype "bidirectional"))
    )
    (net (code "161") (name "unconnected-(U3-A8-Pad9)") (class "Default")
      (node (ref "U3") (pin "9") (pinfunction "A8_9") (pintype "bidirectional"))
    )
  )
)
